# singleboard.net
KiCad netlist of a schematic drawn in EAGLE
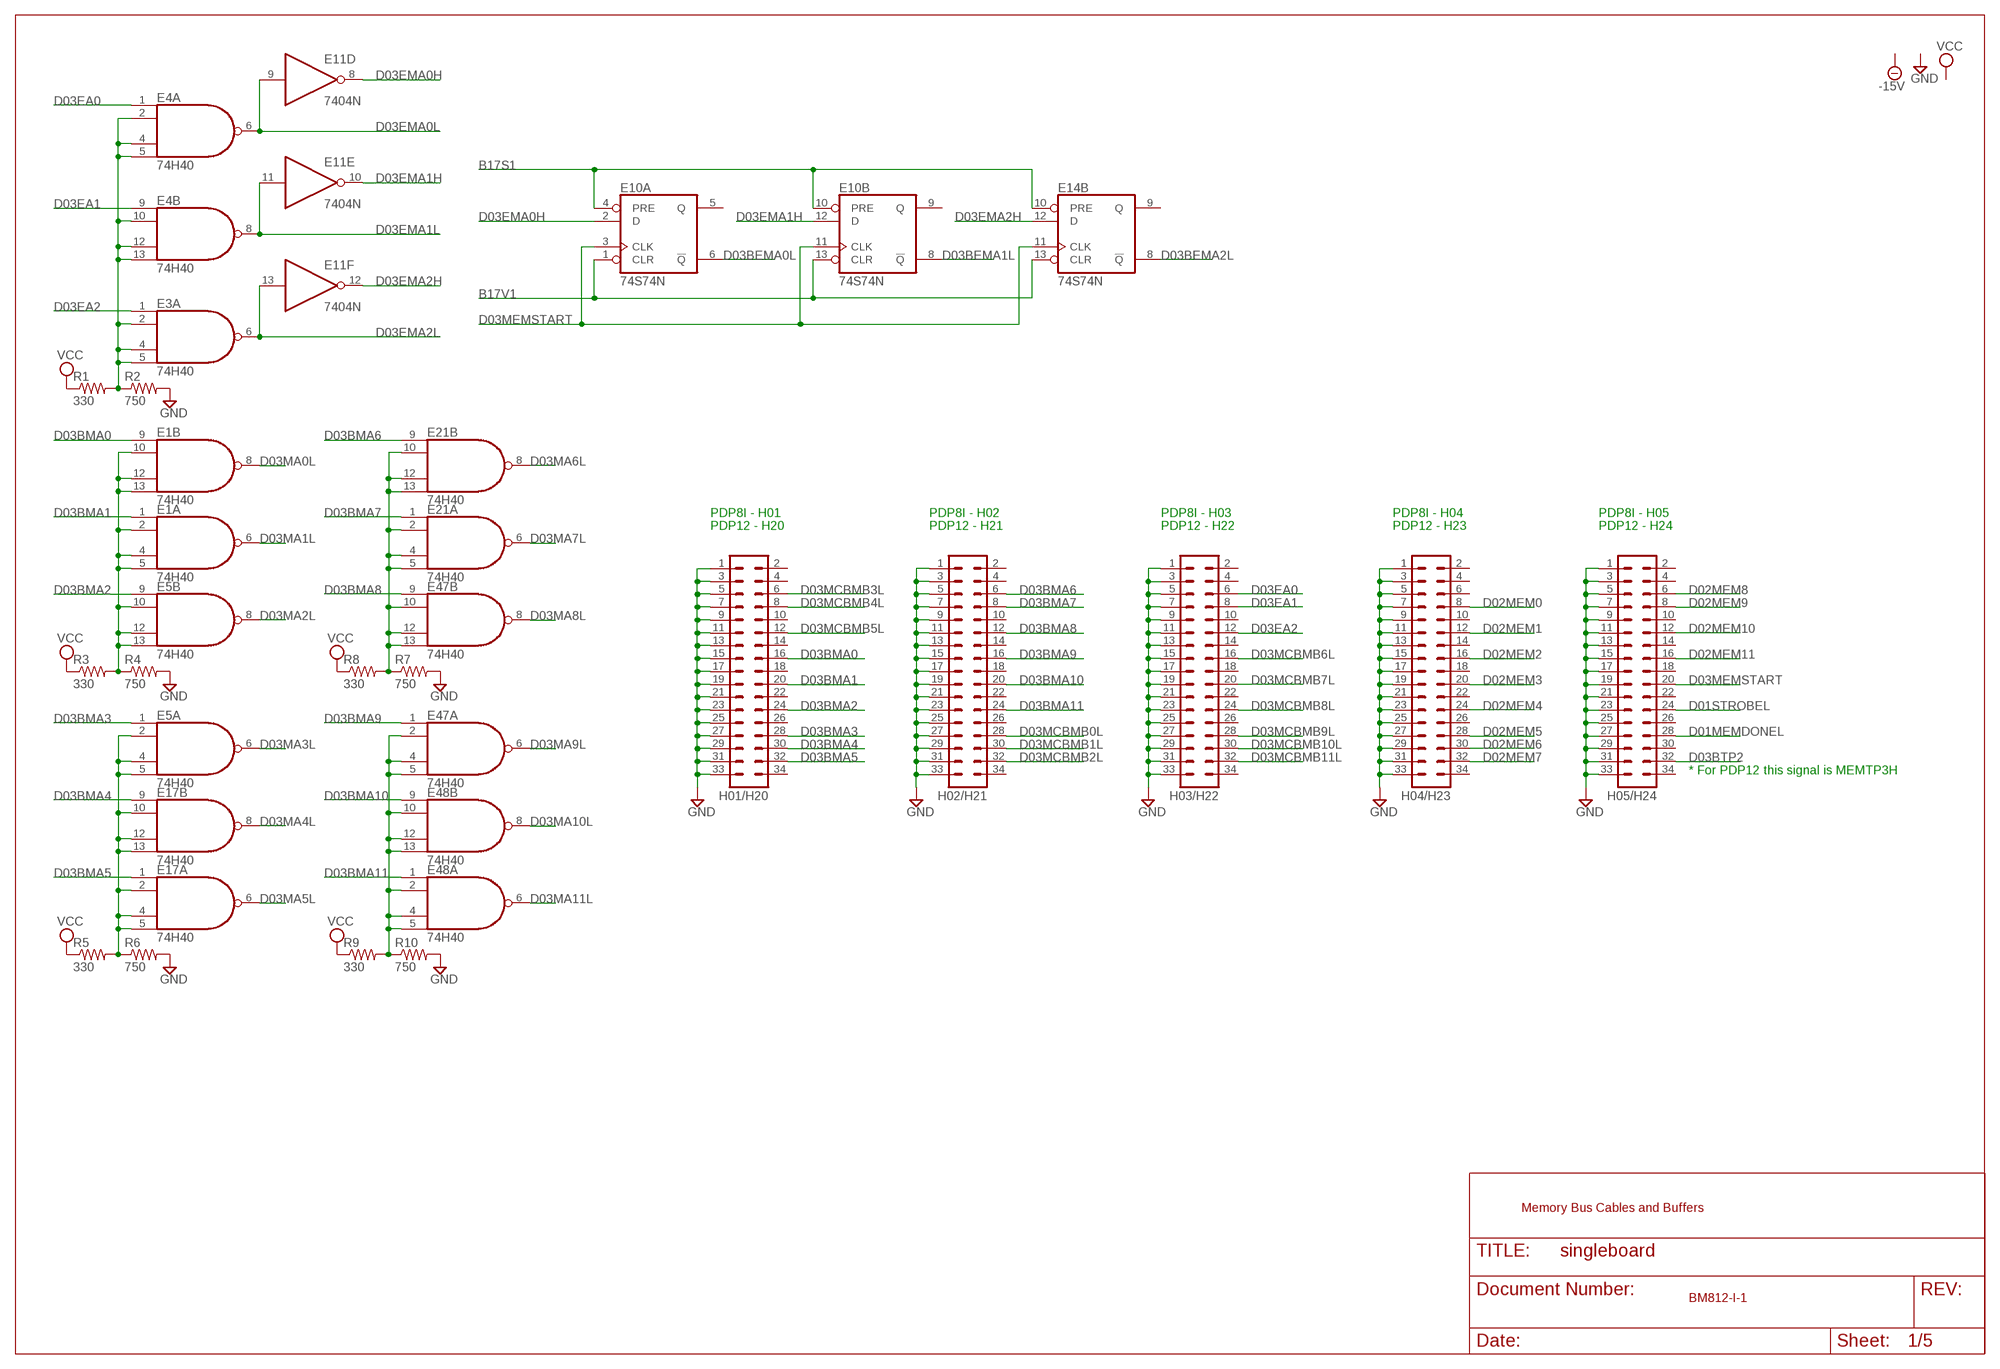
[diagram p0: schematic, sheet 1]
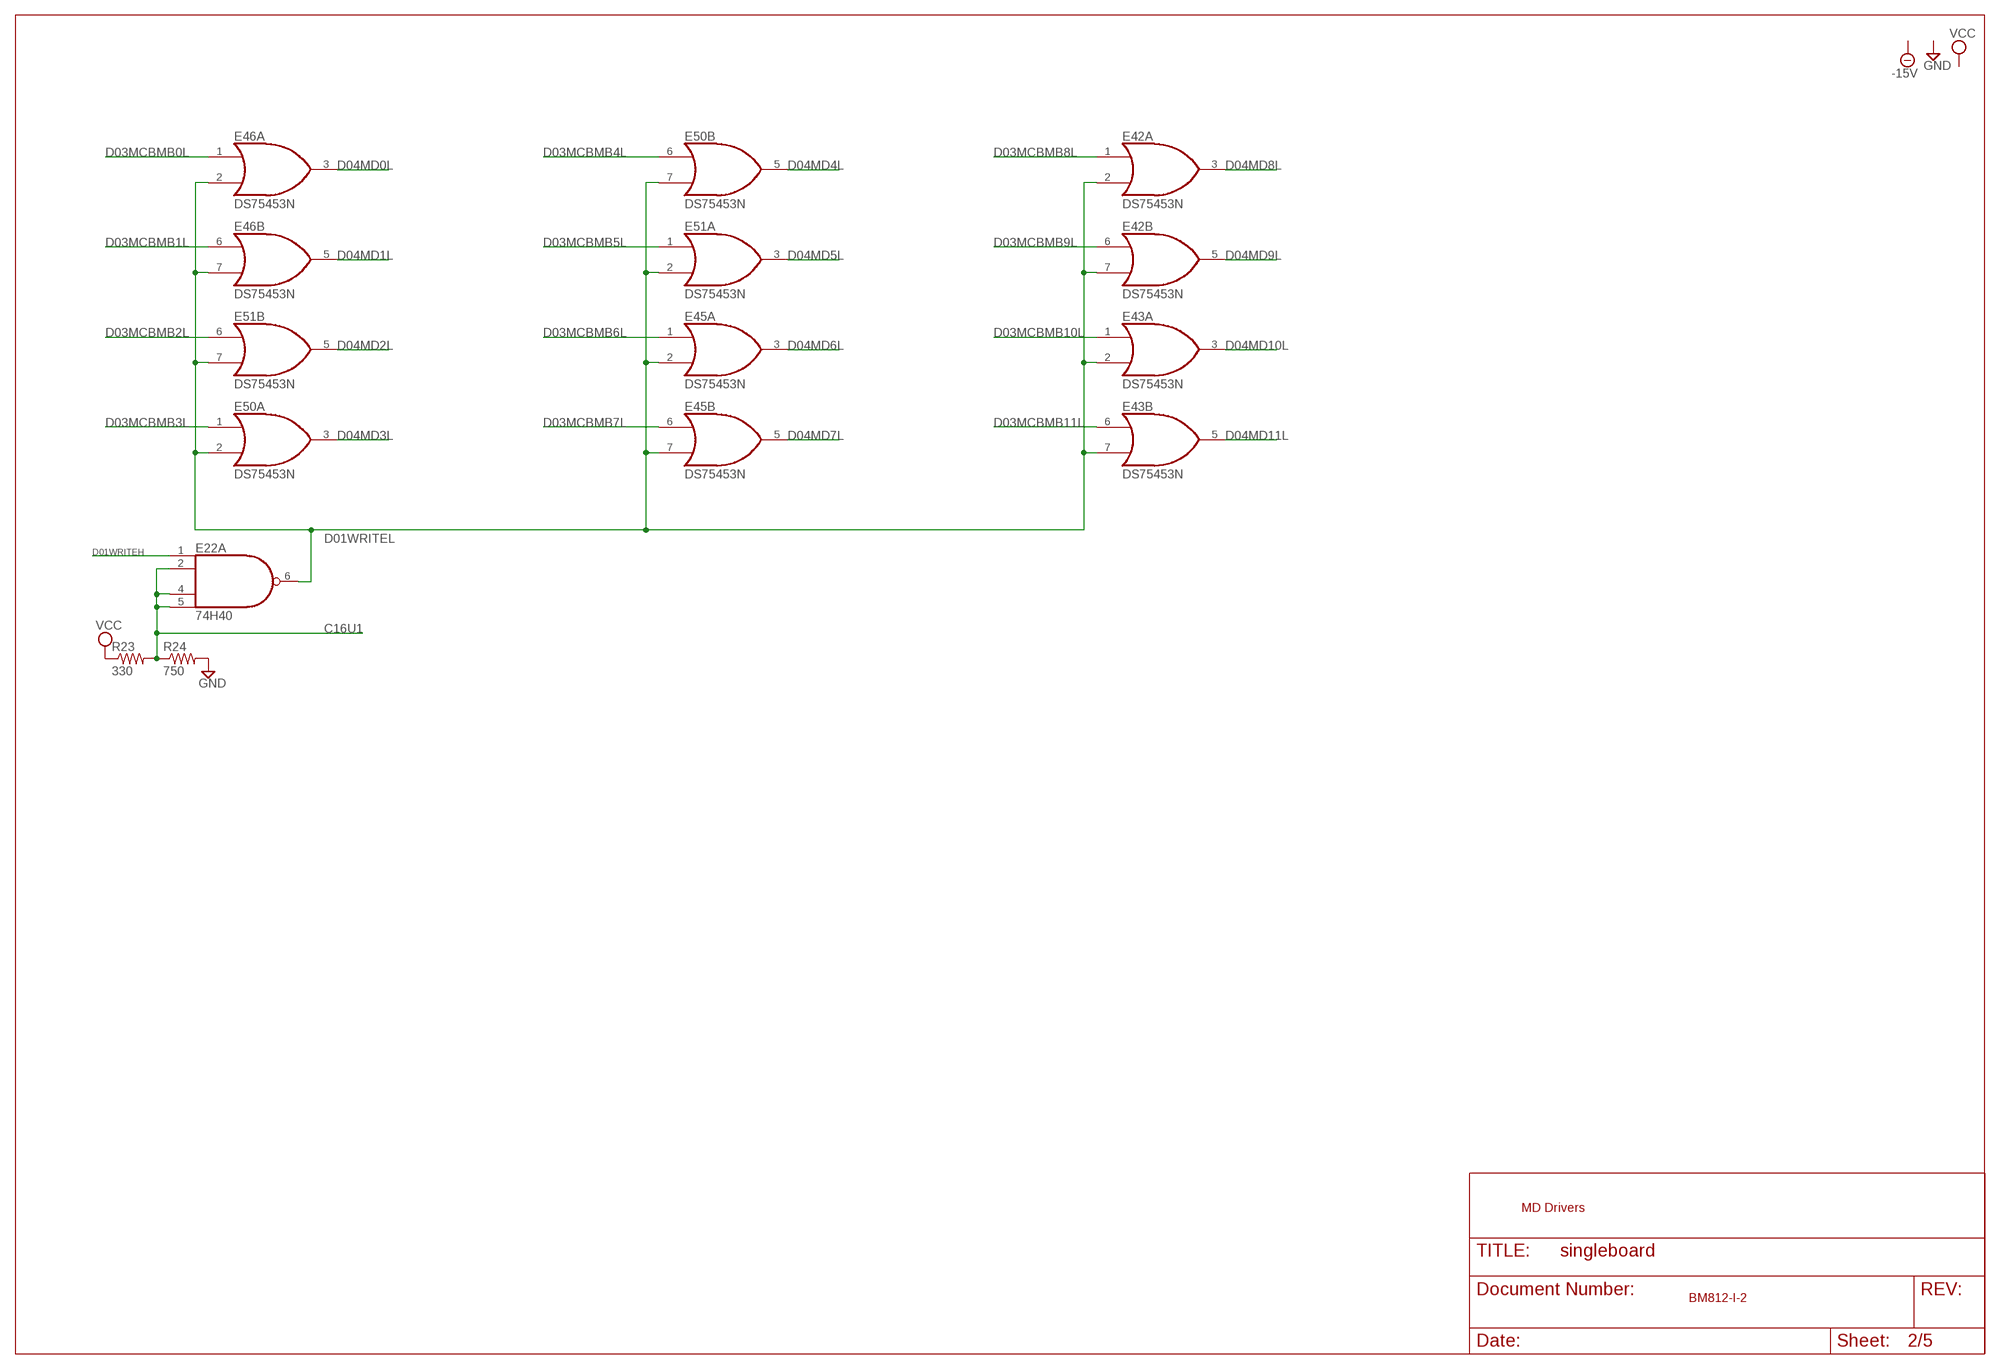
[diagram p1: schematic, sheet 2]
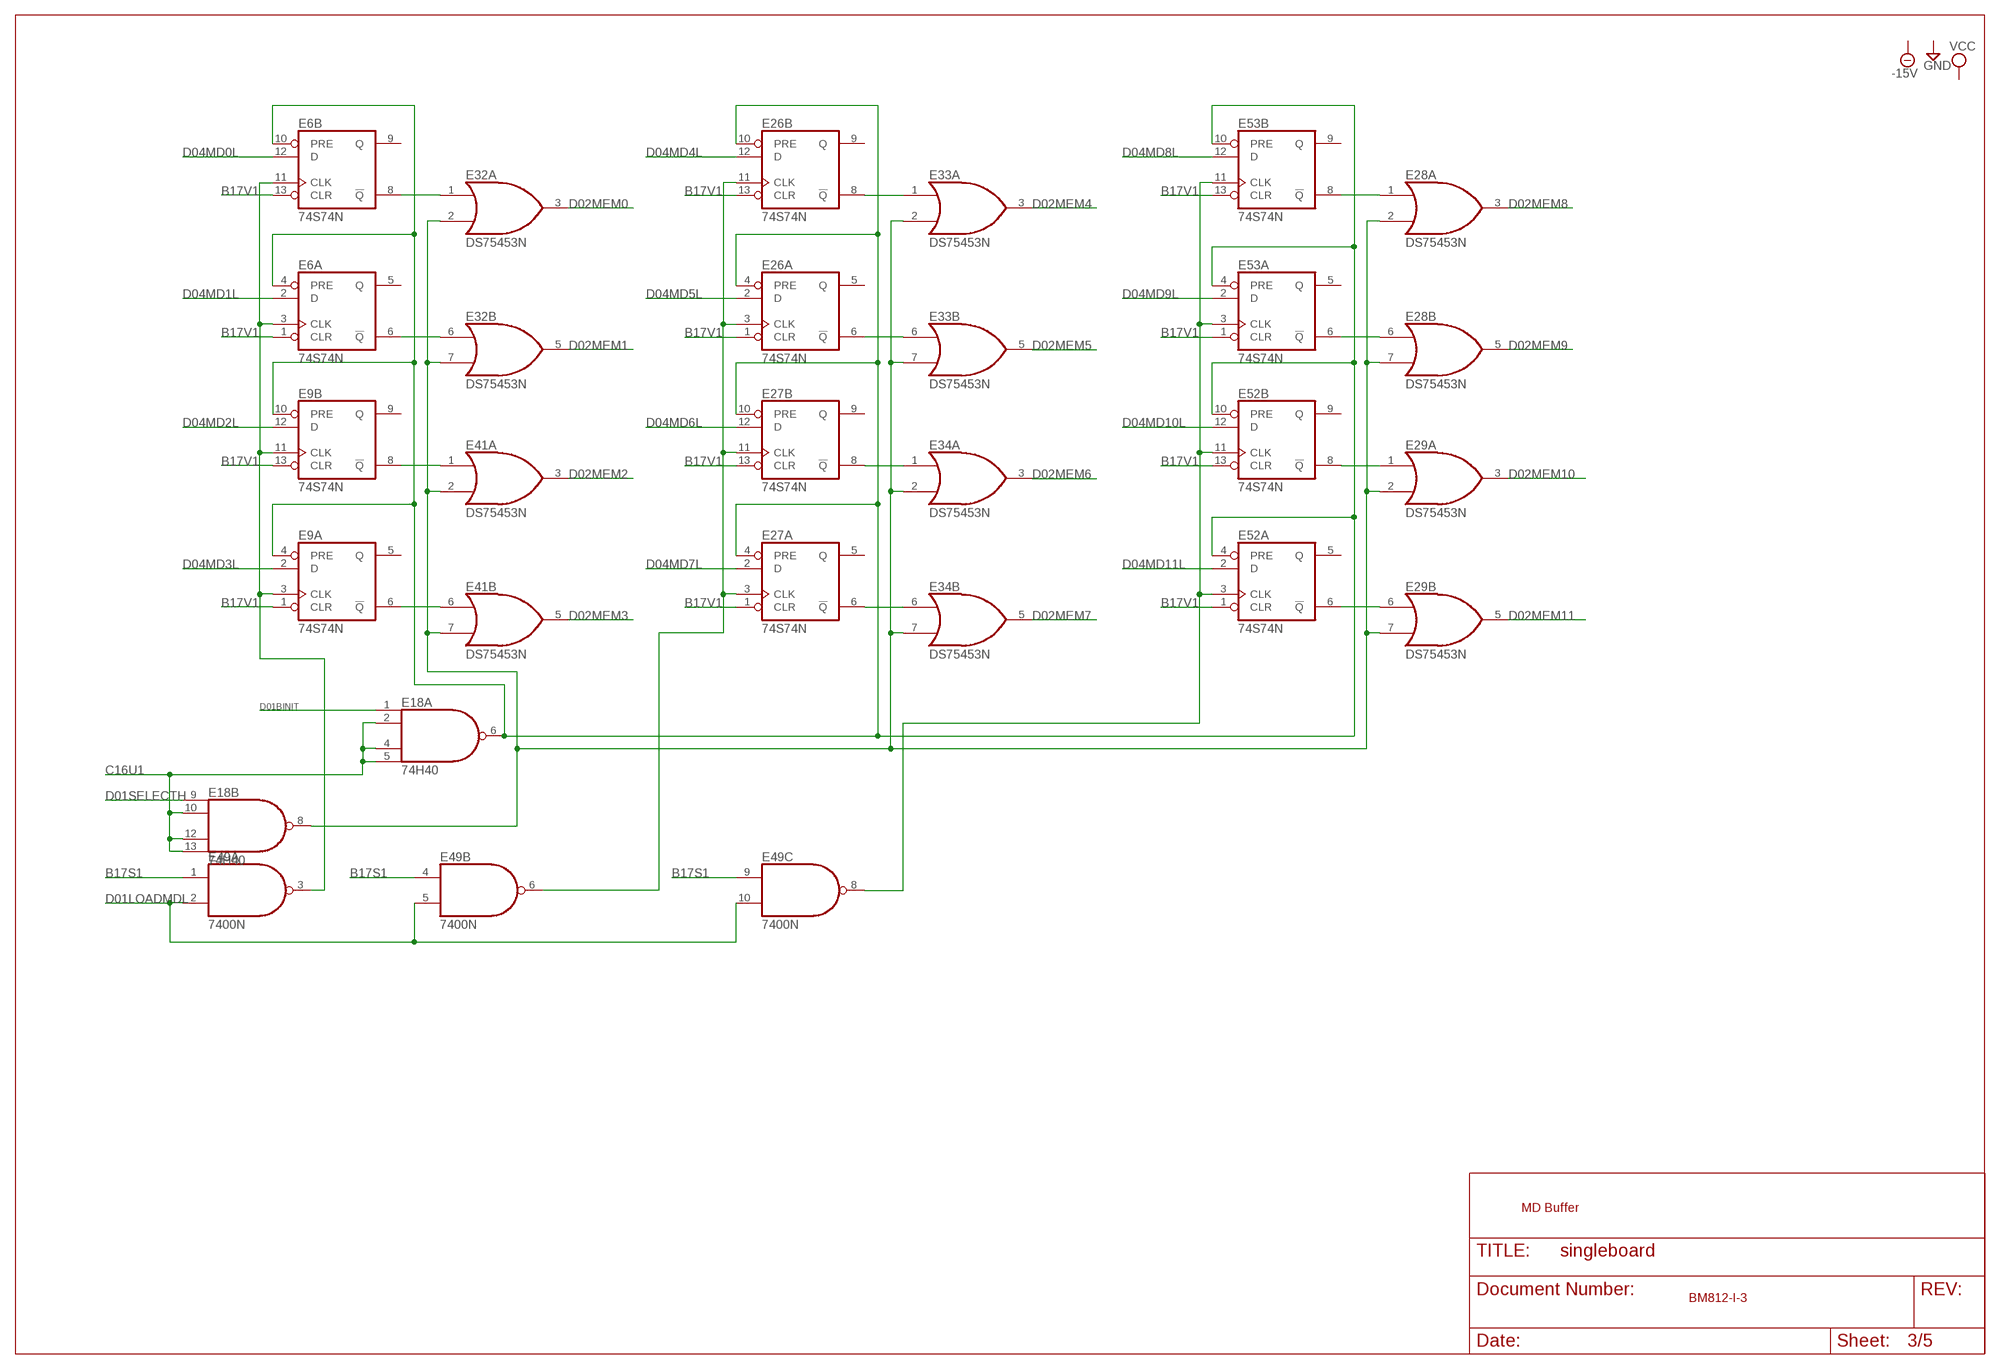
[diagram p2: schematic, sheet 3]
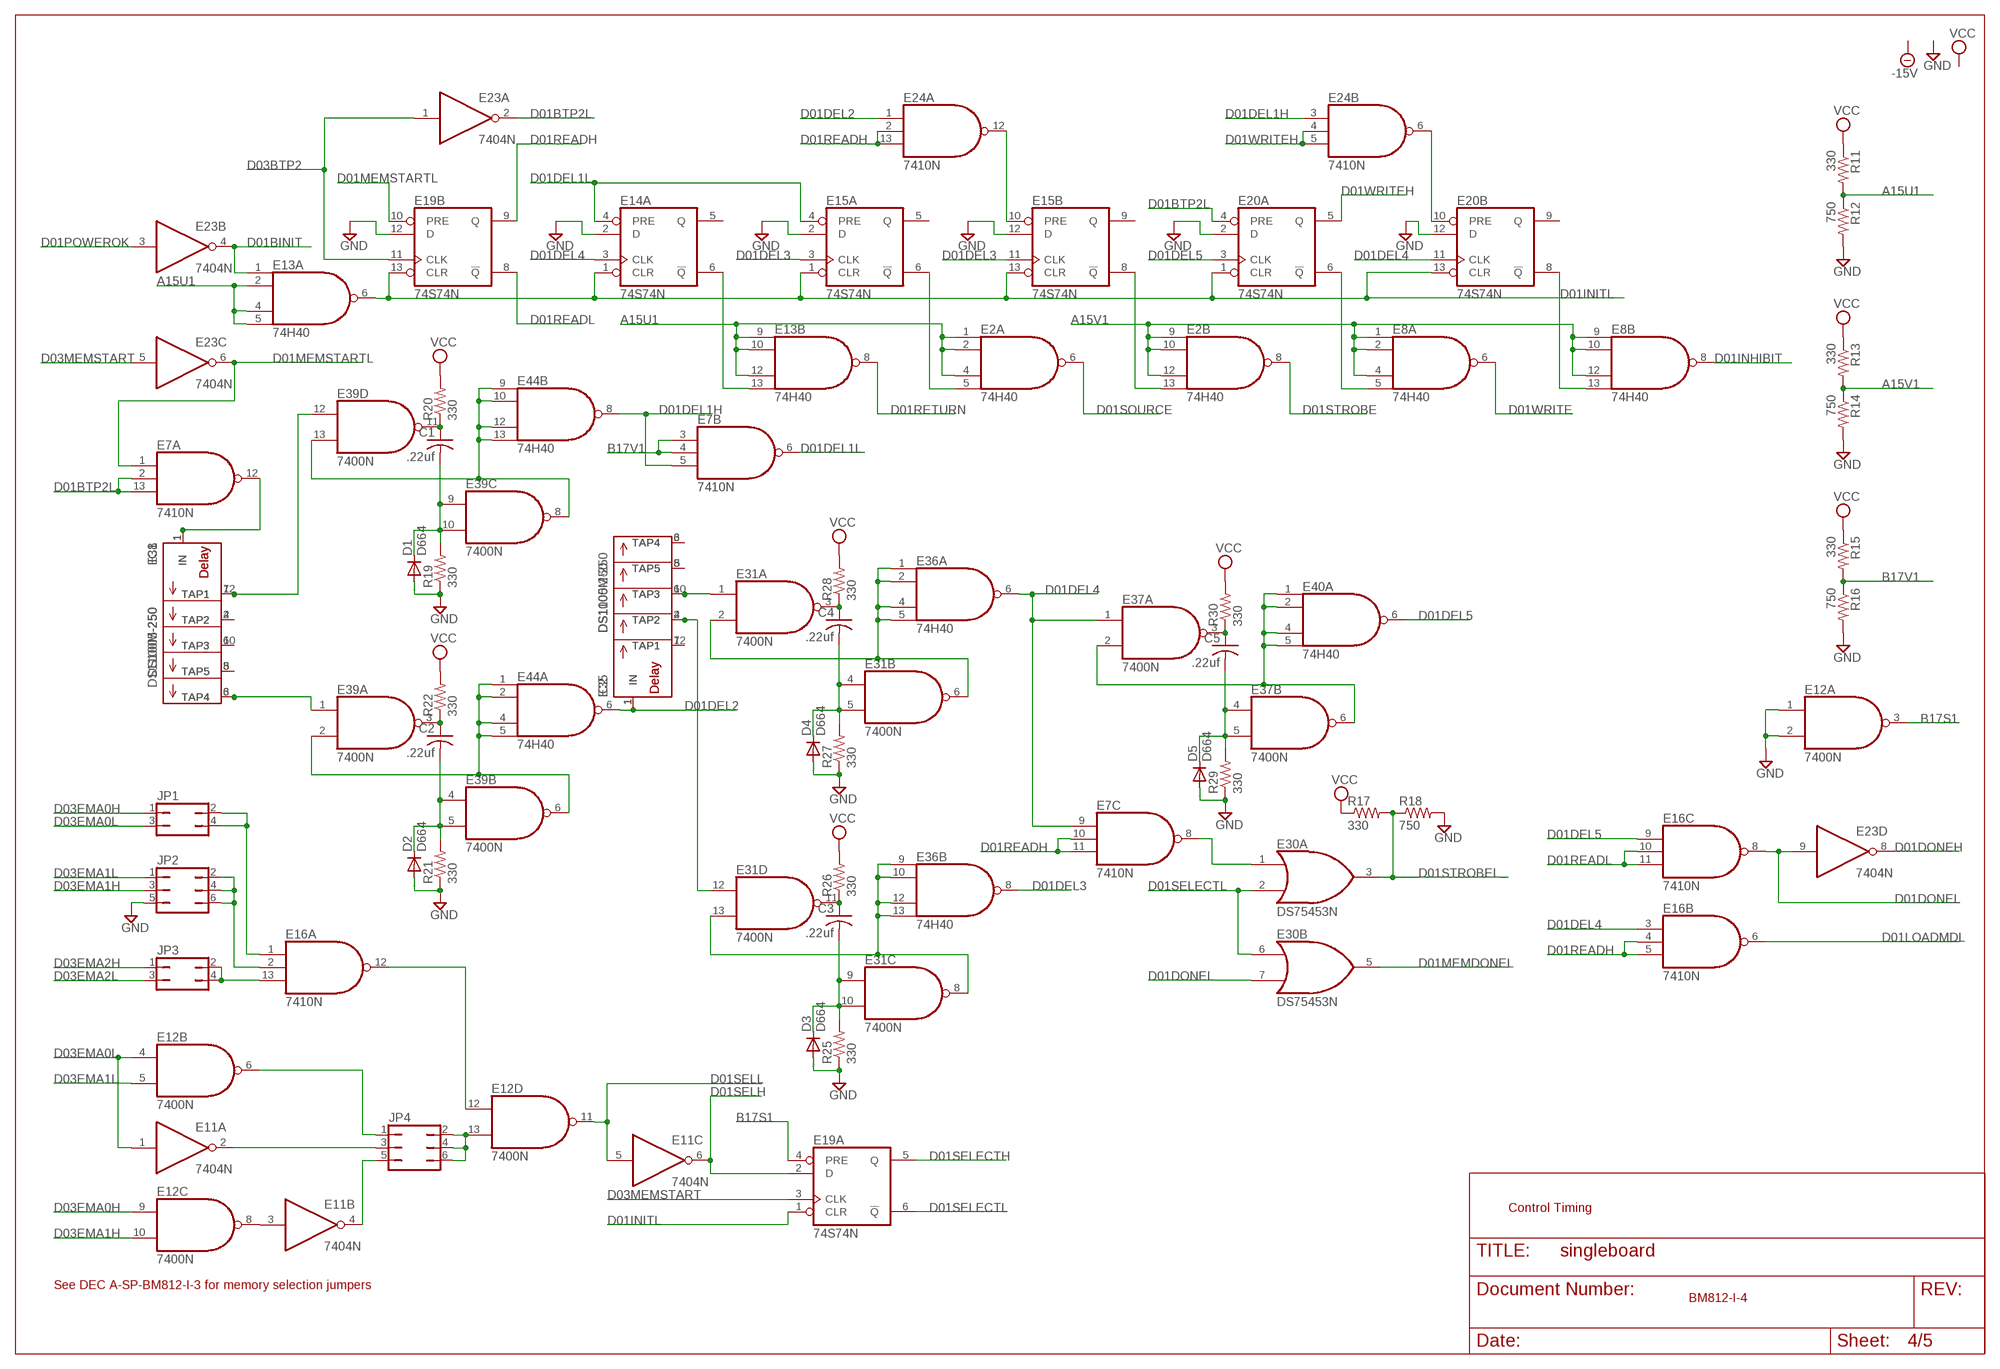
[diagram p3: schematic, sheet 4]
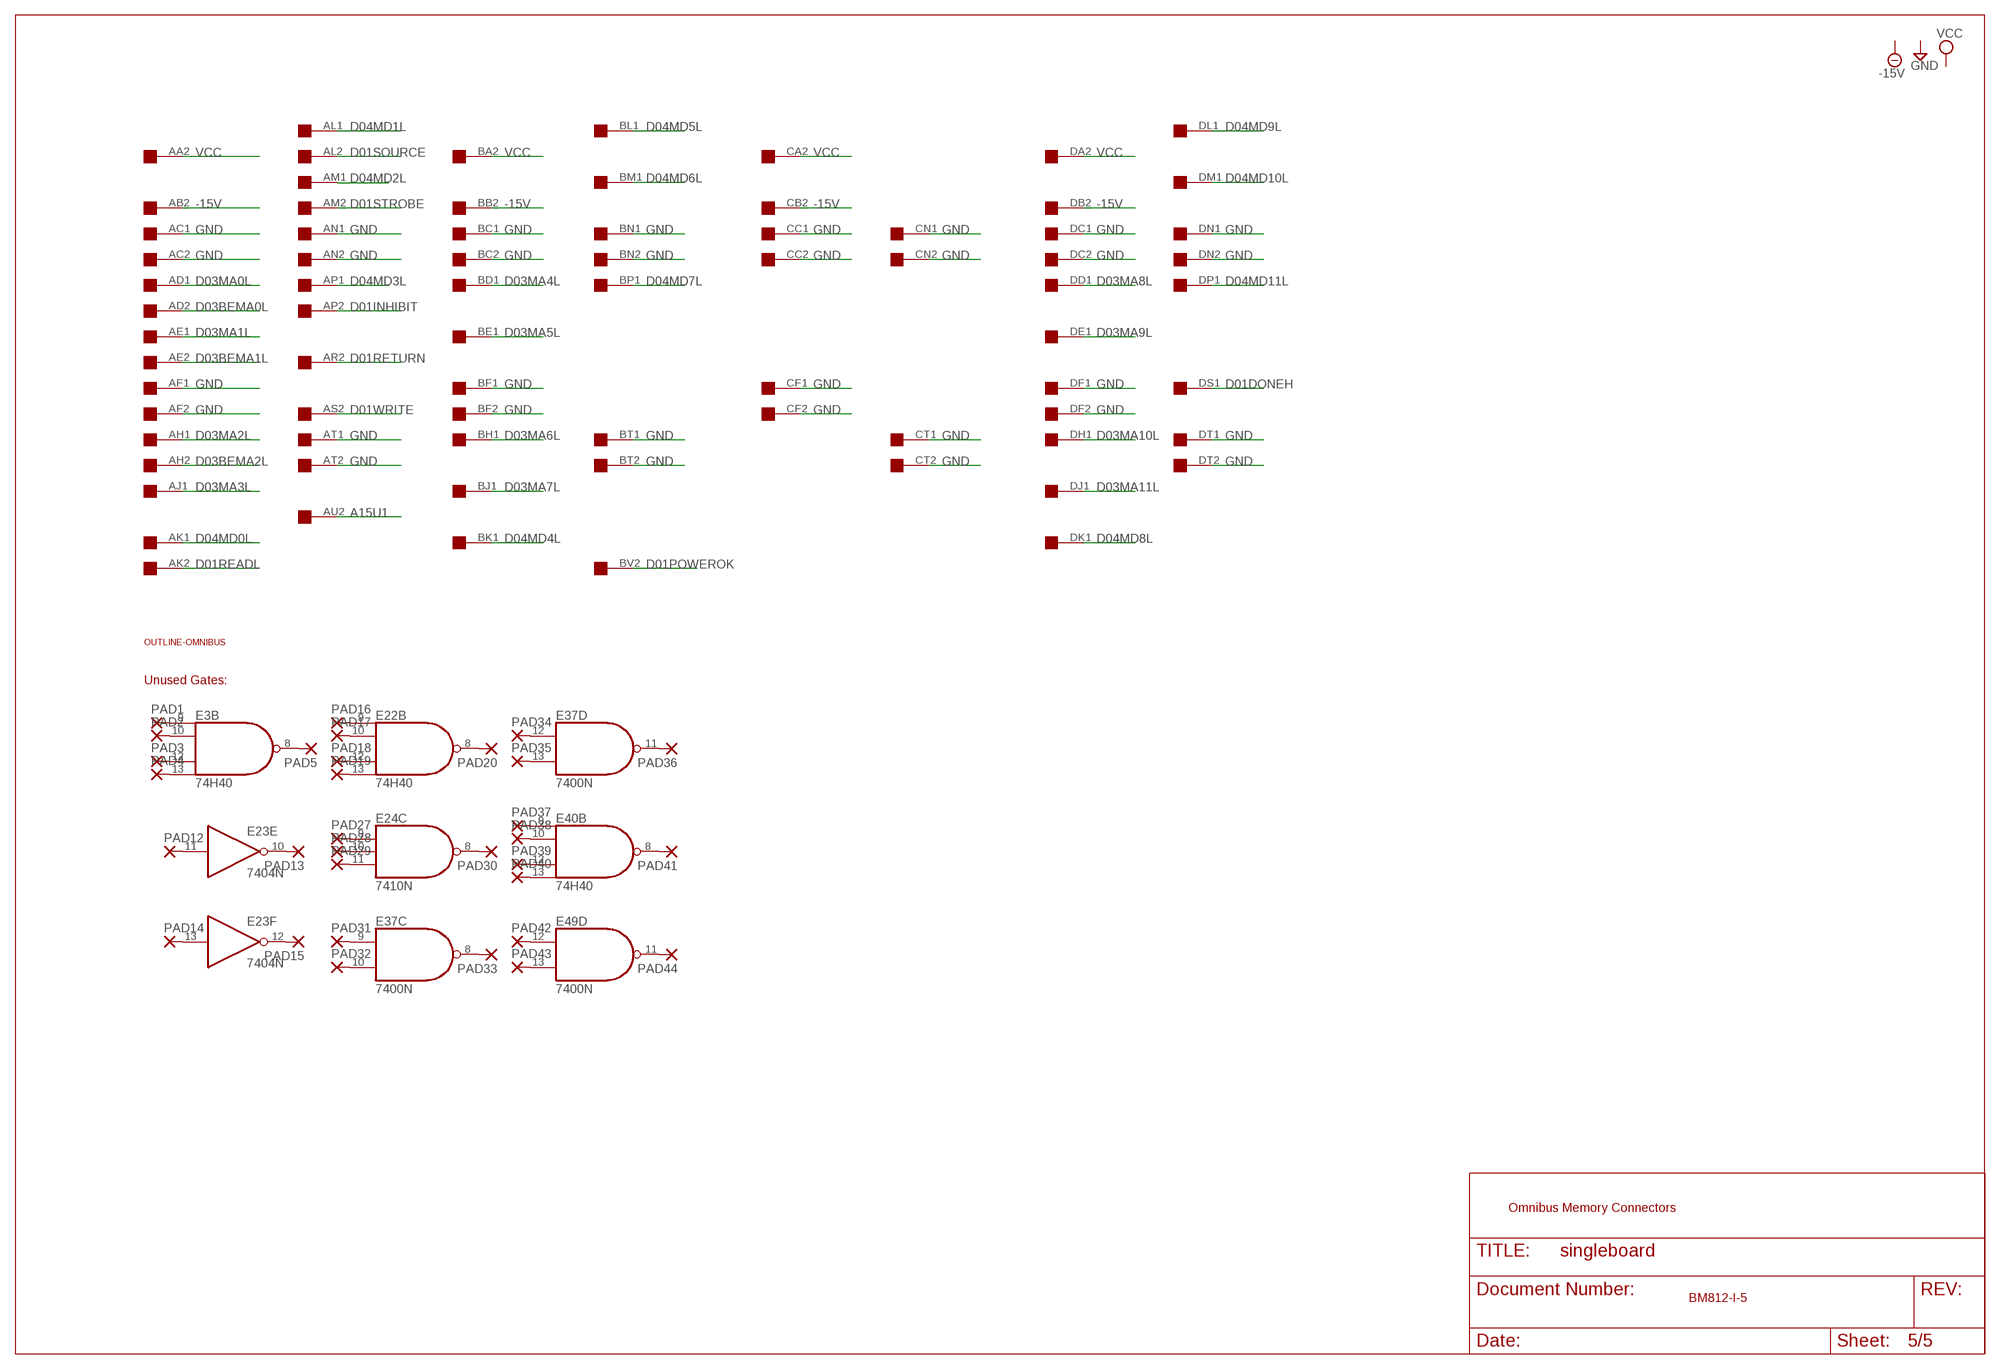
[diagram p4: schematic, sheet 5]

(export (version "E")
  (design (tool "Eeschema 10.0.6"))
  (components
    (comp (ref "E6")
      (value "74S74N")
      (footprint "eagle-import:DIL14")
      (libsource (lib "eagle-import") (part "7474NS"))
    )
    (comp (ref "E9")
      (value "74S74N")
      (footprint "eagle-import:DIL14")
      (libsource (lib "eagle-import") (part "7474NS"))
    )
    (comp (ref "E18")
      (value "74H40")
      (footprint "eagle-import:DIL14")
      (libsource (lib "eagle-import") (part "7420NS"))
    )
    (comp (ref "E26")
      (value "74S74N")
      (footprint "eagle-import:DIL14")
      (libsource (lib "eagle-import") (part "7474NS"))
    )
    (comp (ref "E27")
      (value "74S74N")
      (footprint "eagle-import:DIL14")
      (libsource (lib "eagle-import") (part "7474NS"))
    )
    (comp (ref "E28")
      (value "DS75453N")
      (footprint "eagle-import:DIL08")
      (libsource (lib "eagle-import") (part "DS75453N"))
    )
    (comp (ref "E29")
      (value "DS75453N")
      (footprint "eagle-import:DIL08")
      (libsource (lib "eagle-import") (part "DS75453N"))
    )
    (comp (ref "E32")
      (value "DS75453N")
      (footprint "eagle-import:DIL08")
      (libsource (lib "eagle-import") (part "DS75453N"))
    )
    (comp (ref "E33")
      (value "DS75453N")
      (footprint "eagle-import:DIL08")
      (libsource (lib "eagle-import") (part "DS75453N"))
    )
    (comp (ref "E34")
      (value "DS75453N")
      (footprint "eagle-import:DIL08")
      (libsource (lib "eagle-import") (part "DS75453N"))
    )
    (comp (ref "E41")
      (value "DS75453N")
      (footprint "eagle-import:DIL08")
      (libsource (lib "eagle-import") (part "DS75453N"))
    )
    (comp (ref "E49")
      (value "7400N")
      (footprint "eagle-import:DIL14")
      (libsource (lib "eagle-import") (part "7400N"))
    )
    (comp (ref "E52")
      (value "74S74N")
      (footprint "eagle-import:DIL14")
      (libsource (lib "eagle-import") (part "7474NS"))
    )
    (comp (ref "E53")
      (value "74S74N")
      (footprint "eagle-import:DIL14")
      (libsource (lib "eagle-import") (part "7474NS"))
    )
    (comp (ref "E22")
      (value "74H40")
      (footprint "eagle-import:DIL14")
      (libsource (lib "eagle-import") (part "7420NS"))
    )
    (comp (ref "E42")
      (value "DS75453N")
      (footprint "eagle-import:DIL08")
      (libsource (lib "eagle-import") (part "DS75453N"))
    )
    (comp (ref "E43")
      (value "DS75453N")
      (footprint "eagle-import:DIL08")
      (libsource (lib "eagle-import") (part "DS75453N"))
    )
    (comp (ref "E45")
      (value "DS75453N")
      (footprint "eagle-import:DIL08")
      (libsource (lib "eagle-import") (part "DS75453N"))
    )
    (comp (ref "E46")
      (value "DS75453N")
      (footprint "eagle-import:DIL08")
      (libsource (lib "eagle-import") (part "DS75453N"))
    )
    (comp (ref "E50")
      (value "DS75453N")
      (footprint "eagle-import:DIL08")
      (libsource (lib "eagle-import") (part "DS75453N"))
    )
    (comp (ref "E51")
      (value "DS75453N")
      (footprint "eagle-import:DIL08")
      (libsource (lib "eagle-import") (part "DS75453N"))
    )
    (comp (ref "R23")
      (value "330")
      (footprint "eagle-import:0207_10")
      (libsource (lib "eagle-import") (part "R-US_0207/10"))
    )
    (comp (ref "R24")
      (value "750")
      (footprint "eagle-import:0207_10")
      (libsource (lib "eagle-import") (part "R-US_0207/10"))
    )
    (comp (ref "E3")
      (value "74H40")
      (footprint "eagle-import:DIL14")
      (libsource (lib "eagle-import") (part "7420NS"))
    )
    (comp (ref "E23")
      (value "7404N")
      (footprint "eagle-import:DIL14")
      (libsource (lib "eagle-import") (part "7404N"))
    )
    (comp (ref "E24")
      (value "7410N")
      (footprint "eagle-import:DIL14")
      (libsource (lib "eagle-import") (part "7410N"))
    )
    (comp (ref "E37")
      (value "7400N")
      (footprint "eagle-import:DIL14")
      (libsource (lib "eagle-import") (part "7400N"))
    )
    (comp (ref "E40")
      (value "74H40")
      (footprint "eagle-import:DIL14")
      (libsource (lib "eagle-import") (part "7420NS"))
    )
    (comp (ref "PAD1")
      (value "1,6/0,8")
      (footprint "eagle-import:1,6_0,8")
      (libsource (lib "eagle-import") (part "1,6/0,8"))
    )
    (comp (ref "PAD2")
      (value "1,6/0,8")
      (footprint "eagle-import:1,6_0,8")
      (libsource (lib "eagle-import") (part "1,6/0,8"))
    )
    (comp (ref "PAD3")
      (value "1,6/0,8")
      (footprint "eagle-import:1,6_0,8")
      (libsource (lib "eagle-import") (part "1,6/0,8"))
    )
    (comp (ref "PAD4")
      (value "1,6/0,8")
      (footprint "eagle-import:1,6_0,8")
      (libsource (lib "eagle-import") (part "1,6/0,8"))
    )
    (comp (ref "PAD5")
      (value "1,6/0,8")
      (footprint "eagle-import:1,6_0,8")
      (libsource (lib "eagle-import") (part "1,6/0,8"))
    )
    (comp (ref "PAD12")
      (value "1,6/0,8")
      (footprint "eagle-import:1,6_0,8")
      (libsource (lib "eagle-import") (part "1,6/0,8"))
    )
    (comp (ref "PAD13")
      (value "1,6/0,8")
      (footprint "eagle-import:1,6_0,8")
      (libsource (lib "eagle-import") (part "1,6/0,8"))
    )
    (comp (ref "PAD14")
      (value "1,6/0,8")
      (footprint "eagle-import:1,6_0,8")
      (libsource (lib "eagle-import") (part "1,6/0,8"))
    )
    (comp (ref "PAD15")
      (value "1,6/0,8")
      (footprint "eagle-import:1,6_0,8")
      (libsource (lib "eagle-import") (part "1,6/0,8"))
    )
    (comp (ref "PAD16")
      (value "1,6/0,8")
      (footprint "eagle-import:1,6_0,8")
      (libsource (lib "eagle-import") (part "1,6/0,8"))
    )
    (comp (ref "PAD17")
      (value "1,6/0,8")
      (footprint "eagle-import:1,6_0,8")
      (libsource (lib "eagle-import") (part "1,6/0,8"))
    )
    (comp (ref "PAD18")
      (value "1,6/0,8")
      (footprint "eagle-import:1,6_0,8")
      (libsource (lib "eagle-import") (part "1,6/0,8"))
    )
    (comp (ref "PAD19")
      (value "1,6/0,8")
      (footprint "eagle-import:1,6_0,8")
      (libsource (lib "eagle-import") (part "1,6/0,8"))
    )
    (comp (ref "PAD20")
      (value "1,6/0,8")
      (footprint "eagle-import:1,6_0,8")
      (libsource (lib "eagle-import") (part "1,6/0,8"))
    )
    (comp (ref "PAD27")
      (value "1,6/0,8")
      (footprint "eagle-import:1,6_0,8")
      (libsource (lib "eagle-import") (part "1,6/0,8"))
    )
    (comp (ref "PAD28")
      (value "1,6/0,8")
      (footprint "eagle-import:1,6_0,8")
      (libsource (lib "eagle-import") (part "1,6/0,8"))
    )
    (comp (ref "PAD29")
      (value "1,6/0,8")
      (footprint "eagle-import:1,6_0,8")
      (libsource (lib "eagle-import") (part "1,6/0,8"))
    )
    (comp (ref "PAD30")
      (value "1,6/0,8")
      (footprint "eagle-import:1,6_0,8")
      (libsource (lib "eagle-import") (part "1,6/0,8"))
    )
    (comp (ref "PAD31")
      (value "1,6/0,8")
      (footprint "eagle-import:1,6_0,8")
      (libsource (lib "eagle-import") (part "1,6/0,8"))
    )
    (comp (ref "PAD32")
      (value "1,6/0,8")
      (footprint "eagle-import:1,6_0,8")
      (libsource (lib "eagle-import") (part "1,6/0,8"))
    )
    (comp (ref "PAD33")
      (value "1,6/0,8")
      (footprint "eagle-import:1,6_0,8")
      (libsource (lib "eagle-import") (part "1,6/0,8"))
    )
    (comp (ref "PAD34")
      (value "1,6/0,8")
      (footprint "eagle-import:1,6_0,8")
      (libsource (lib "eagle-import") (part "1,6/0,8"))
    )
    (comp (ref "PAD35")
      (value "1,6/0,8")
      (footprint "eagle-import:1,6_0,8")
      (libsource (lib "eagle-import") (part "1,6/0,8"))
    )
    (comp (ref "PAD36")
      (value "1,6/0,8")
      (footprint "eagle-import:1,6_0,8")
      (libsource (lib "eagle-import") (part "1,6/0,8"))
    )
    (comp (ref "PAD37")
      (value "1,6/0,8")
      (footprint "eagle-import:1,6_0,8")
      (libsource (lib "eagle-import") (part "1,6/0,8"))
    )
    (comp (ref "PAD38")
      (value "1,6/0,8")
      (footprint "eagle-import:1,6_0,8")
      (libsource (lib "eagle-import") (part "1,6/0,8"))
    )
    (comp (ref "PAD39")
      (value "1,6/0,8")
      (footprint "eagle-import:1,6_0,8")
      (libsource (lib "eagle-import") (part "1,6/0,8"))
    )
    (comp (ref "PAD40")
      (value "1,6/0,8")
      (footprint "eagle-import:1,6_0,8")
      (libsource (lib "eagle-import") (part "1,6/0,8"))
    )
    (comp (ref "PAD41")
      (value "1,6/0,8")
      (footprint "eagle-import:1,6_0,8")
      (libsource (lib "eagle-import") (part "1,6/0,8"))
    )
    (comp (ref "PAD42")
      (value "1,6/0,8")
      (footprint "eagle-import:1,6_0,8")
      (libsource (lib "eagle-import") (part "1,6/0,8"))
    )
    (comp (ref "PAD43")
      (value "1,6/0,8")
      (footprint "eagle-import:1,6_0,8")
      (libsource (lib "eagle-import") (part "1,6/0,8"))
    )
    (comp (ref "PAD44")
      (value "1,6/0,8")
      (footprint "eagle-import:1,6_0,8")
      (libsource (lib "eagle-import") (part "1,6/0,8"))
    )
    (comp (ref "U$1")
      (value "QUAD")
      (footprint "eagle-import:EDGE-CON8")
      (libsource (lib "eagle-import") (part "QUAD"))
    )
    (comp (ref "U$2")
      (value "OUTLINE-OMNIBUS")
      (footprint "eagle-import:OMNIBUS")
      (libsource (lib "eagle-import") (part "OUTLINE-OMNIBUS"))
    )
    (comp (ref "C1")
      (value ".22uf")
      (footprint "eagle-import:C050-025X075")
      (libsource (lib "eagle-import") (part "C-US050-025X075"))
    )
    (comp (ref "C2")
      (value ".22uf")
      (footprint "eagle-import:C050-025X075")
      (libsource (lib "eagle-import") (part "C-US050-025X075"))
    )
    (comp (ref "C3")
      (value ".22uf")
      (footprint "eagle-import:C050-025X075")
      (libsource (lib "eagle-import") (part "C-US050-025X075"))
    )
    (comp (ref "C4")
      (value ".22uf")
      (footprint "eagle-import:C050-025X075")
      (libsource (lib "eagle-import") (part "C-US050-025X075"))
    )
    (comp (ref "C5")
      (value ".22uf")
      (footprint "eagle-import:C050-025X075")
      (libsource (lib "eagle-import") (part "C-US050-025X075"))
    )
    (comp (ref "D1")
      (value "D664")
      (footprint "eagle-import:DO35-10")
      (libsource (lib "eagle-import") (part "1N4148DO35-10"))
    )
    (comp (ref "D2")
      (value "D664")
      (footprint "eagle-import:DO35-10")
      (libsource (lib "eagle-import") (part "1N4148DO35-10"))
    )
    (comp (ref "D3")
      (value "D664")
      (footprint "eagle-import:DO35-10")
      (libsource (lib "eagle-import") (part "1N4148DO35-10"))
    )
    (comp (ref "D4")
      (value "D664")
      (footprint "eagle-import:DO35-10")
      (libsource (lib "eagle-import") (part "1N4148DO35-10"))
    )
    (comp (ref "D5")
      (value "D664")
      (footprint "eagle-import:DO35-10")
      (libsource (lib "eagle-import") (part "1N4148DO35-10"))
    )
    (comp (ref "E2")
      (value "74H40")
      (footprint "eagle-import:DIL14")
      (libsource (lib "eagle-import") (part "7420NS"))
    )
    (comp (ref "E7")
      (value "7410N")
      (footprint "eagle-import:DIL14")
      (libsource (lib "eagle-import") (part "7410N"))
    )
    (comp (ref "E8")
      (value "74H40")
      (footprint "eagle-import:DIL14")
      (libsource (lib "eagle-import") (part "7420NS"))
    )
    (comp (ref "E11")
      (value "7404N")
      (footprint "eagle-import:DIL14")
      (libsource (lib "eagle-import") (part "7404N"))
    )
    (comp (ref "E12")
      (value "7400N")
      (footprint "eagle-import:DIL14")
      (libsource (lib "eagle-import") (part "7400N"))
    )
    (comp (ref "E13")
      (value "74H40")
      (footprint "eagle-import:DIL14")
      (libsource (lib "eagle-import") (part "7420NS"))
    )
    (comp (ref "E14")
      (value "74S74N")
      (footprint "eagle-import:DIL14")
      (libsource (lib "eagle-import") (part "7474NS"))
    )
    (comp (ref "E15")
      (value "74S74N")
      (footprint "eagle-import:DIL14")
      (libsource (lib "eagle-import") (part "7474NS"))
    )
    (comp (ref "E16")
      (value "7410N")
      (footprint "eagle-import:DIL14")
      (libsource (lib "eagle-import") (part "7410N"))
    )
    (comp (ref "E19")
      (value "74S74N")
      (footprint "eagle-import:DIL14")
      (libsource (lib "eagle-import") (part "7474NS"))
    )
    (comp (ref "E20")
      (value "74S74N")
      (footprint "eagle-import:DIL14")
      (libsource (lib "eagle-import") (part "7474NS"))
    )
    (comp (ref "E30")
      (value "DS75453N")
      (footprint "eagle-import:DIL08")
      (libsource (lib "eagle-import") (part "DS75453N"))
    )
    (comp (ref "E31")
      (value "7400N")
      (footprint "eagle-import:DIL14")
      (libsource (lib "eagle-import") (part "7400N"))
    )
    (comp (ref "E35")
      (value "DS1005-250")
      (footprint "eagle-import:DIL14")
      (libsource (lib "eagle-import") (part "MXD1000P"))
    )
    (comp (ref "E36")
      (value "74H40")
      (footprint "eagle-import:DIL14")
      (libsource (lib "eagle-import") (part "7420NS"))
    )
    (comp (ref "E38")
      (value "DS1005-250")
      (footprint "eagle-import:DIL14")
      (libsource (lib "eagle-import") (part "MXD1000P"))
    )
    (comp (ref "E39")
      (value "7400N")
      (footprint "eagle-import:DIL14")
      (libsource (lib "eagle-import") (part "7400N"))
    )
    (comp (ref "E44")
      (value "74H40")
      (footprint "eagle-import:DIL14")
      (libsource (lib "eagle-import") (part "7420NS"))
    )
    (comp (ref "IC1")
      (value "DS1100M-250")
      (footprint "eagle-import:DIL08")
      (libsource (lib "eagle-import") (part "MXD1000"))
    )
    (comp (ref "IC2")
      (value "DS1100M-250")
      (footprint "eagle-import:DIL08")
      (libsource (lib "eagle-import") (part "MXD1000"))
    )
    (comp (ref "JP1")
      (value "JP2Q")
      (footprint "eagle-import:JP2Q")
      (libsource (lib "eagle-import") (part "JP2Q"))
    )
    (comp (ref "JP2")
      (value "JP3Q")
      (footprint "eagle-import:JP3Q")
      (libsource (lib "eagle-import") (part "JP3Q"))
    )
    (comp (ref "JP3")
      (value "JP2Q")
      (footprint "eagle-import:JP2Q")
      (libsource (lib "eagle-import") (part "JP2Q"))
    )
    (comp (ref "JP4")
      (value "JP3Q")
      (footprint "eagle-import:JP3Q")
      (libsource (lib "eagle-import") (part "JP3Q"))
    )
    (comp (ref "R11")
      (value "330")
      (footprint "eagle-import:0207_10")
      (libsource (lib "eagle-import") (part "R-US_0207/10"))
    )
    (comp (ref "R12")
      (value "750")
      (footprint "eagle-import:0207_10")
      (libsource (lib "eagle-import") (part "R-US_0207/10"))
    )
    (comp (ref "R13")
      (value "330")
      (footprint "eagle-import:0207_10")
      (libsource (lib "eagle-import") (part "R-US_0207/10"))
    )
    (comp (ref "R14")
      (value "750")
      (footprint "eagle-import:0207_10")
      (libsource (lib "eagle-import") (part "R-US_0207/10"))
    )
    (comp (ref "R15")
      (value "330")
      (footprint "eagle-import:0207_10")
      (libsource (lib "eagle-import") (part "R-US_0207/10"))
    )
    (comp (ref "R16")
      (value "750")
      (footprint "eagle-import:0207_10")
      (libsource (lib "eagle-import") (part "R-US_0207/10"))
    )
    (comp (ref "R17")
      (value "330")
      (footprint "eagle-import:0207_10")
      (libsource (lib "eagle-import") (part "R-US_0207/10"))
    )
    (comp (ref "R18")
      (value "750")
      (footprint "eagle-import:0207_10")
      (libsource (lib "eagle-import") (part "R-US_0207/10"))
    )
    (comp (ref "R19")
      (value "330")
      (footprint "eagle-import:0207_10")
      (libsource (lib "eagle-import") (part "R-US_0207/10"))
    )
    (comp (ref "R20")
      (value "330")
      (footprint "eagle-import:0207_10")
      (libsource (lib "eagle-import") (part "R-US_0207/10"))
    )
    (comp (ref "R21")
      (value "330")
      (footprint "eagle-import:0207_10")
      (libsource (lib "eagle-import") (part "R-US_0207/10"))
    )
    (comp (ref "R22")
      (value "330")
      (footprint "eagle-import:0207_10")
      (libsource (lib "eagle-import") (part "R-US_0207/10"))
    )
    (comp (ref "R25")
      (value "330")
      (footprint "eagle-import:0207_10")
      (libsource (lib "eagle-import") (part "R-US_0207/10"))
    )
    (comp (ref "R26")
      (value "330")
      (footprint "eagle-import:0207_10")
      (libsource (lib "eagle-import") (part "R-US_0207/10"))
    )
    (comp (ref "R27")
      (value "330")
      (footprint "eagle-import:0207_10")
      (libsource (lib "eagle-import") (part "R-US_0207/10"))
    )
    (comp (ref "R28")
      (value "330")
      (footprint "eagle-import:0207_10")
      (libsource (lib "eagle-import") (part "R-US_0207/10"))
    )
    (comp (ref "R29")
      (value "330")
      (footprint "eagle-import:0207_10")
      (libsource (lib "eagle-import") (part "R-US_0207/10"))
    )
    (comp (ref "R30")
      (value "330")
      (footprint "eagle-import:0207_10")
      (libsource (lib "eagle-import") (part "R-US_0207/10"))
    )
    (comp (ref "E1")
      (value "74H40")
      (footprint "eagle-import:DIL14")
      (libsource (lib "eagle-import") (part "7420NS"))
    )
    (comp (ref "E4")
      (value "74H40")
      (footprint "eagle-import:DIL14")
      (libsource (lib "eagle-import") (part "7420NS"))
    )
    (comp (ref "E5")
      (value "74H40")
      (footprint "eagle-import:DIL14")
      (libsource (lib "eagle-import") (part "7420NS"))
    )
    (comp (ref "E10")
      (value "74S74N")
      (footprint "eagle-import:DIL14")
      (libsource (lib "eagle-import") (part "7474NS"))
    )
    (comp (ref "E17")
      (value "74H40")
      (footprint "eagle-import:DIL14")
      (libsource (lib "eagle-import") (part "7420NS"))
    )
    (comp (ref "E21")
      (value "74H40")
      (footprint "eagle-import:DIL14")
      (libsource (lib "eagle-import") (part "7420NS"))
    )
    (comp (ref "E47")
      (value "74H40")
      (footprint "eagle-import:DIL14")
      (libsource (lib "eagle-import") (part "7420NS"))
    )
    (comp (ref "E48")
      (value "74H40")
      (footprint "eagle-import:DIL14")
      (libsource (lib "eagle-import") (part "7420NS"))
    )
    (comp (ref "H01/H20")
      (value "MA17-2")
      (footprint "eagle-import:MA17-2")
      (libsource (lib "eagle-import") (part "MA17-2"))
    )
    (comp (ref "H02/H21")
      (value "MA17-2")
      (footprint "eagle-import:MA17-2")
      (libsource (lib "eagle-import") (part "MA17-2"))
    )
    (comp (ref "H03/H22")
      (value "MA17-2")
      (footprint "eagle-import:MA17-2")
      (libsource (lib "eagle-import") (part "MA17-2"))
    )
    (comp (ref "H04/H23")
      (value "MA17-2")
      (footprint "eagle-import:MA17-2")
      (libsource (lib "eagle-import") (part "MA17-2"))
    )
    (comp (ref "H05/H24")
      (value "MA17-2")
      (footprint "eagle-import:MA17-2")
      (libsource (lib "eagle-import") (part "MA17-2"))
    )
    (comp (ref "R1")
      (value "330")
      (footprint "eagle-import:0207_10")
      (libsource (lib "eagle-import") (part "R-US_0207/10"))
    )
    (comp (ref "R2")
      (value "750")
      (footprint "eagle-import:0207_10")
      (libsource (lib "eagle-import") (part "R-US_0207/10"))
    )
    (comp (ref "R3")
      (value "330")
      (footprint "eagle-import:0207_10")
      (libsource (lib "eagle-import") (part "R-US_0207/10"))
    )
    (comp (ref "R4")
      (value "750")
      (footprint "eagle-import:0207_10")
      (libsource (lib "eagle-import") (part "R-US_0207/10"))
    )
    (comp (ref "R5")
      (value "330")
      (footprint "eagle-import:0207_10")
      (libsource (lib "eagle-import") (part "R-US_0207/10"))
    )
    (comp (ref "R6")
      (value "750")
      (footprint "eagle-import:0207_10")
      (libsource (lib "eagle-import") (part "R-US_0207/10"))
    )
    (comp (ref "R7")
      (value "750")
      (footprint "eagle-import:0207_10")
      (libsource (lib "eagle-import") (part "R-US_0207/10"))
    )
    (comp (ref "R8")
      (value "330")
      (footprint "eagle-import:0207_10")
      (libsource (lib "eagle-import") (part "R-US_0207/10"))
    )
    (comp (ref "R9")
      (value "330")
      (footprint "eagle-import:0207_10")
      (libsource (lib "eagle-import") (part "R-US_0207/10"))
    )
    (comp (ref "R10")
      (value "750")
      (footprint "eagle-import:0207_10")
      (libsource (lib "eagle-import") (part "R-US_0207/10"))
    )
  )
  (nets
    (net (code "1") (name "-15V") (class "Default")
      (node (ref "U$1") (pin "AB2") (pinfunction "1_AB2") (pintype "bidirectional"))
      (node (ref "U$1") (pin "BB2") (pinfunction "1_BB2") (pintype "bidirectional"))
      (node (ref "U$1") (pin "CB2") (pinfunction "1_CB2") (pintype "bidirectional"))
      (node (ref "U$1") (pin "DB2") (pinfunction "1_DB2") (pintype "bidirectional"))
    )
    (net (code "2") (name "A15U1") (class "Default")
      (node (ref "E13") (pin "10") (pinfunction "I1_10") (pintype "input"))
      (node (ref "E13") (pin "12") (pinfunction "I2_12") (pintype "input"))
      (node (ref "E13") (pin "2") (pinfunction "I1_2") (pintype "input"))
      (node (ref "E13") (pin "4") (pinfunction "I2_4") (pintype "input"))
      (node (ref "E13") (pin "5") (pinfunction "I3_5") (pintype "input"))
      (node (ref "E13") (pin "9") (pinfunction "I0_9") (pintype "input"))
      (node (ref "E2") (pin "1") (pinfunction "I0_1") (pintype "input"))
      (node (ref "E2") (pin "2") (pinfunction "I1_2") (pintype "input"))
      (node (ref "E2") (pin "4") (pinfunction "I2_4") (pintype "input"))
      (node (ref "R11") (pin "2") (pinfunction "2_2") (pintype "passive"))
      (node (ref "R12") (pin "1") (pinfunction "1_1") (pintype "passive"))
      (node (ref "U$1") (pin "AU2") (pinfunction "1_AU2") (pintype "bidirectional"))
    )
    (net (code "3") (name "A15V1") (class "Default")
      (node (ref "E2") (pin "10") (pinfunction "I1_10") (pintype "input"))
      (node (ref "E2") (pin "12") (pinfunction "I2_12") (pintype "input"))
      (node (ref "E2") (pin "9") (pinfunction "I0_9") (pintype "input"))
      (node (ref "E8") (pin "1") (pinfunction "I0_1") (pintype "input"))
      (node (ref "E8") (pin "10") (pinfunction "I1_10") (pintype "input"))
      (node (ref "E8") (pin "12") (pinfunction "I2_12") (pintype "input"))
      (node (ref "E8") (pin "2") (pinfunction "I1_2") (pintype "input"))
      (node (ref "E8") (pin "4") (pinfunction "I2_4") (pintype "input"))
      (node (ref "E8") (pin "9") (pinfunction "I0_9") (pintype "input"))
      (node (ref "R13") (pin "2") (pinfunction "2_2") (pintype "passive"))
      (node (ref "R14") (pin "1") (pinfunction "1_1") (pintype "passive"))
    )
    (net (code "4") (name "B17S1") (class "Default")
      (node (ref "E10") (pin "10") (pinfunction "PRE_10") (pintype "input"))
      (node (ref "E10") (pin "4") (pinfunction "PRE_4") (pintype "input"))
      (node (ref "E12") (pin "3") (pinfunction "O_3") (pintype "output"))
      (node (ref "E14") (pin "10") (pinfunction "PRE_10") (pintype "input"))
      (node (ref "E19") (pin "4") (pinfunction "PRE_4") (pintype "input"))
      (node (ref "E49") (pin "1") (pinfunction "I0_1") (pintype "input"))
      (node (ref "E49") (pin "4") (pinfunction "I0_4") (pintype "input"))
      (node (ref "E49") (pin "9") (pinfunction "I0_9") (pintype "input"))
    )
    (net (code "5") (name "B17V1") (class "Default")
      (node (ref "E10") (pin "1") (pinfunction "CLR_1") (pintype "input"))
      (node (ref "E10") (pin "13") (pinfunction "CLR_13") (pintype "input"))
      (node (ref "E14") (pin "13") (pinfunction "CLR_13") (pintype "input"))
      (node (ref "E26") (pin "1") (pinfunction "CLR_1") (pintype "input"))
      (node (ref "E26") (pin "13") (pinfunction "CLR_13") (pintype "input"))
      (node (ref "E27") (pin "1") (pinfunction "CLR_1") (pintype "input"))
      (node (ref "E27") (pin "13") (pinfunction "CLR_13") (pintype "input"))
      (node (ref "E52") (pin "1") (pinfunction "CLR_1") (pintype "input"))
      (node (ref "E52") (pin "13") (pinfunction "CLR_13") (pintype "input"))
      (node (ref "E53") (pin "1") (pinfunction "CLR_1") (pintype "input"))
      (node (ref "E53") (pin "13") (pinfunction "CLR_13") (pintype "input"))
      (node (ref "E6") (pin "1") (pinfunction "CLR_1") (pintype "input"))
      (node (ref "E6") (pin "13") (pinfunction "CLR_13") (pintype "input"))
      (node (ref "E7") (pin "3") (pinfunction "I0_3") (pintype "input"))
      (node (ref "E7") (pin "4") (pinfunction "I1_4") (pintype "input"))
      (node (ref "E9") (pin "1") (pinfunction "CLR_1") (pintype "input"))
      (node (ref "E9") (pin "13") (pinfunction "CLR_13") (pintype "input"))
      (node (ref "R15") (pin "2") (pinfunction "2_2") (pintype "passive"))
      (node (ref "R16") (pin "1") (pinfunction "1_1") (pintype "passive"))
    )
    (net (code "6") (name "C16U1") (class "Default")
      (node (ref "E18") (pin "10") (pinfunction "I1_10") (pintype "input"))
      (node (ref "E18") (pin "12") (pinfunction "I2_12") (pintype "input"))
      (node (ref "E18") (pin "13") (pinfunction "I3_13") (pintype "input"))
      (node (ref "E18") (pin "2") (pinfunction "I1_2") (pintype "input"))
      (node (ref "E18") (pin "4") (pinfunction "I2_4") (pintype "input"))
      (node (ref "E18") (pin "5") (pinfunction "I3_5") (pintype "input"))
      (node (ref "E22") (pin "2") (pinfunction "I1_2") (pintype "input"))
      (node (ref "E22") (pin "4") (pinfunction "I2_4") (pintype "input"))
      (node (ref "E22") (pin "5") (pinfunction "I3_5") (pintype "input"))
      (node (ref "R23") (pin "2") (pinfunction "2_2") (pintype "passive"))
      (node (ref "R24") (pin "1") (pinfunction "1_1") (pintype "passive"))
    )
    (net (code "7") (name "D01BINIT") (class "Default")
      (node (ref "E13") (pin "1") (pinfunction "I0_1") (pintype "input"))
      (node (ref "E18") (pin "1") (pinfunction "I0_1") (pintype "input"))
      (node (ref "E23") (pin "4") (pinfunction "O_4") (pintype "output"))
    )
    (net (code "8") (name "D01BTP2L") (class "Default")
      (node (ref "E20") (pin "4") (pinfunction "PRE_4") (pintype "input"))
      (node (ref "E23") (pin "2") (pinfunction "O_2") (pintype "output"))
      (node (ref "E7") (pin "13") (pinfunction "I2_13") (pintype "input"))
      (node (ref "E7") (pin "2") (pinfunction "I1_2") (pintype "input"))
    )
    (net (code "9") (name "D01DEL1H") (class "Default")
      (node (ref "E24") (pin "3") (pinfunction "I0_3") (pintype "input"))
      (node (ref "E44") (pin "8") (pinfunction "O_8") (pintype "output"))
      (node (ref "E7") (pin "5") (pinfunction "I2_5") (pintype "input"))
    )
    (net (code "10") (name "D01DEL1L") (class "Default")
      (node (ref "E14") (pin "4") (pinfunction "PRE_4") (pintype "input"))
      (node (ref "E15") (pin "4") (pinfunction "PRE_4") (pintype "input"))
      (node (ref "E7") (pin "6") (pinfunction "O_6") (pintype "output"))
    )
    (net (code "11") (name "D01DEL2") (class "Default")
      (node (ref "E24") (pin "1") (pinfunction "I0_1") (pintype "input"))
      (node (ref "E35") (pin "1") (pinfunction "IN_1") (pintype "input"))
      (node (ref "E44") (pin "6") (pinfunction "O_6") (pintype "output"))
      (node (ref "IC2") (pin "1") (pinfunction "IN_1") (pintype "input"))
    )
    (net (code "12") (name "D01DEL3") (class "Default")
      (node (ref "E15") (pin "11") (pinfunction "CLK_11") (pintype "input"))
      (node (ref "E15") (pin "3") (pinfunction "CLK_3") (pintype "input"))
      (node (ref "E36") (pin "8") (pinfunction "O_8") (pintype "output"))
    )
    (net (code "13") (name "D01DEL4") (class "Default")
      (node (ref "E14") (pin "3") (pinfunction "CLK_3") (pintype "input"))
      (node (ref "E16") (pin "3") (pinfunction "I0_3") (pintype "input"))
      (node (ref "E20") (pin "11") (pinfunction "CLK_11") (pintype "input"))
      (node (ref "E36") (pin "6") (pinfunction "O_6") (pintype "output"))
      (node (ref "E37") (pin "1") (pinfunction "I0_1") (pintype "input"))
      (node (ref "E7") (pin "9") (pinfunction "I0_9") (pintype "input"))
    )
    (net (code "14") (name "D01DEL5") (class "Default")
      (node (ref "E16") (pin "9") (pinfunction "I0_9") (pintype "input"))
      (node (ref "E20") (pin "3") (pinfunction "CLK_3") (pintype "input"))
      (node (ref "E40") (pin "6") (pinfunction "O_6") (pintype "output"))
    )
    (net (code "15") (name "D01DONEH") (class "Default")
      (node (ref "E23") (pin "8") (pinfunction "O_8") (pintype "output"))
      (node (ref "U$1") (pin "DS1") (pinfunction "1_DS1") (pintype "bidirectional"))
    )
    (net (code "16") (name "D01DONEL") (class "Default")
      (node (ref "E16") (pin "8") (pinfunction "O_8") (pintype "output"))
      (node (ref "E23") (pin "9") (pinfunction "I_9") (pintype "input"))
      (node (ref "E30") (pin "7") (pinfunction "I1_7") (pintype "input"))
    )
    (net (code "17") (name "D01INHIBIT") (class "Default")
      (node (ref "E8") (pin "8") (pinfunction "O_8") (pintype "output"))
      (node (ref "U$1") (pin "AP2") (pinfunction "1_AP2") (pintype "bidirectional"))
    )
    (net (code "18") (name "D01INITL") (class "Default")
      (node (ref "E13") (pin "6") (pinfunction "O_6") (pintype "output"))
      (node (ref "E14") (pin "1") (pinfunction "CLR_1") (pintype "input"))
      (node (ref "E15") (pin "1") (pinfunction "CLR_1") (pintype "input"))
      (node (ref "E15") (pin "13") (pinfunction "CLR_13") (pintype "input"))
      (node (ref "E19") (pin "1") (pinfunction "CLR_1") (pintype "input"))
      (node (ref "E19") (pin "13") (pinfunction "CLR_13") (pintype "input"))
      (node (ref "E20") (pin "1") (pinfunction "CLR_1") (pintype "input"))
      (node (ref "E20") (pin "13") (pinfunction "CLR_13") (pintype "input"))
    )
    (net (code "19") (name "D01LOADMDL") (class "Default")
      (node (ref "E16") (pin "6") (pinfunction "O_6") (pintype "output"))
      (node (ref "E49") (pin "10") (pinfunction "I1_10") (pintype "input"))
      (node (ref "E49") (pin "2") (pinfunction "I1_2") (pintype "input"))
      (node (ref "E49") (pin "5") (pinfunction "I1_5") (pintype "input"))
    )
    (net (code "20") (name "D01MEMDONEL") (class "Default")
      (node (ref "E30") (pin "5") (pinfunction "O_5") (pintype "open_collector"))
      (node (ref "H05/H24") (pin "28") (pinfunction "28_28") (pintype "passive"))
    )
    (net (code "21") (name "D01MEMSTARTL") (class "Default")
      (node (ref "E19") (pin "10") (pinfunction "PRE_10") (pintype "input"))
      (node (ref "E23") (pin "6") (pinfunction "O_6") (pintype "output"))
      (node (ref "E7") (pin "1") (pinfunction "I0_1") (pintype "input"))
    )
    (net (code "22") (name "D01POWEROK") (class "Default")
      (node (ref "E23") (pin "3") (pinfunction "I_3") (pintype "input"))
      (node (ref "U$1") (pin "BV2") (pinfunction "1_BV2") (pintype "bidirectional"))
    )
    (net (code "23") (name "D01READH") (class "Default")
      (node (ref "E16") (pin "4") (pinfunction "I1_4") (pintype "input"))
      (node (ref "E16") (pin "5") (pinfunction "I2_5") (pintype "input"))
      (node (ref "E19") (pin "9") (pinfunction "Q_9") (pintype "output"))
      (node (ref "E24") (pin "13") (pinfunction "I2_13") (pintype "input"))
      (node (ref "E24") (pin "2") (pinfunction "I1_2") (pintype "input"))
      (node (ref "E7") (pin "10") (pinfunction "I1_10") (pintype "input"))
      (node (ref "E7") (pin "11") (pinfunction "I2_11") (pintype "input"))
    )
    (net (code "24") (name "D01READL") (class "Default")
      (node (ref "E16") (pin "10") (pinfunction "I1_10") (pintype "input"))
      (node (ref "E16") (pin "11") (pinfunction "I2_11") (pintype "input"))
      (node (ref "E19") (pin "8") (pinfunction "~{Q}_8") (pintype "output"))
      (node (ref "U$1") (pin "AK2") (pinfunction "1_AK2") (pintype "bidirectional"))
    )
    (net (code "25") (name "D01RETURN") (class "Default")
      (node (ref "E13") (pin "8") (pinfunction "O_8") (pintype "output"))
      (node (ref "U$1") (pin "AR2") (pinfunction "1_AR2") (pintype "bidirectional"))
    )
    (net (code "26") (name "D01SELECTH") (class "Default")
      (node (ref "E18") (pin "9") (pinfunction "I0_9") (pintype "input"))
      (node (ref "E19") (pin "5") (pinfunction "Q_5") (pintype "output"))
    )
    (net (code "27") (name "D01SELECTL") (class "Default")
      (node (ref "E19") (pin "6") (pinfunction "~{Q}_6") (pintype "output"))
      (node (ref "E30") (pin "2") (pinfunction "I1_2") (pintype "input"))
      (node (ref "E30") (pin "6") (pinfunction "I0_6") (pintype "input"))
    )
    (net (code "28") (name "D01SELH") (class "Default")
      (node (ref "E11") (pin "6") (pinfunction "O_6") (pintype "output"))
      (node (ref "E19") (pin "2") (pinfunction "D_2") (pintype "input"))
    )
    (net (code "29") (name "D01SELL") (class "Default")
      (node (ref "E11") (pin "5") (pinfunction "I_5") (pintype "input"))
      (node (ref "E12") (pin "11") (pinfunction "O_11") (pintype "output"))
    )
    (net (code "30") (name "D01SOURCE") (class "Default")
      (node (ref "E2") (pin "6") (pinfunction "O_6") (pintype "output"))
      (node (ref "U$1") (pin "AL2") (pinfunction "1_AL2") (pintype "bidirectional"))
    )
    (net (code "31") (name "D01STROBE") (class "Default")
      (node (ref "E2") (pin "8") (pinfunction "O_8") (pintype "output"))
      (node (ref "U$1") (pin "AM2") (pinfunction "1_AM2") (pintype "bidirectional"))
    )
    (net (code "32") (name "D01STROBEL") (class "Default")
      (node (ref "E30") (pin "3") (pinfunction "O_3") (pintype "open_collector"))
      (node (ref "H05/H24") (pin "24") (pinfunction "24_24") (pintype "passive"))
      (node (ref "R17") (pin "2") (pinfunction "2_2") (pintype "passive"))
      (node (ref "R18") (pin "1") (pinfunction "1_1") (pintype "passive"))
    )
    (net (code "33") (name "D01WRITE") (class "Default")
      (node (ref "E8") (pin "6") (pinfunction "O_6") (pintype "output"))
      (node (ref "U$1") (pin "AS2") (pinfunction "1_AS2") (pintype "bidirectional"))
    )
    (net (code "34") (name "D01WRITEH") (class "Default")
      (node (ref "E20") (pin "5") (pinfunction "Q_5") (pintype "output"))
      (node (ref "E22") (pin "1") (pinfunction "I0_1") (pintype "input"))
      (node (ref "E24") (pin "4") (pinfunction "I1_4") (pintype "input"))
      (node (ref "E24") (pin "5") (pinfunction "I2_5") (pintype "input"))
    )
    (net (code "35") (name "D01WRITEL") (class "Default")
      (node (ref "E22") (pin "6") (pinfunction "O_6") (pintype "output"))
      (node (ref "E42") (pin "2") (pinfunction "I1_2") (pintype "input"))
      (node (ref "E42") (pin "7") (pinfunction "I1_7") (pintype "input"))
      (node (ref "E43") (pin "2") (pinfunction "I1_2") (pintype "input"))
      (node (ref "E43") (pin "7") (pinfunction "I1_7") (pintype "input"))
      (node (ref "E45") (pin "2") (pinfunction "I1_2") (pintype "input"))
      (node (ref "E45") (pin "7") (pinfunction "I1_7") (pintype "input"))
      (node (ref "E46") (pin "2") (pinfunction "I1_2") (pintype "input"))
      (node (ref "E46") (pin "7") (pinfunction "I1_7") (pintype "input"))
      (node (ref "E50") (pin "2") (pinfunction "I1_2") (pintype "input"))
      (node (ref "E50") (pin "7") (pinfunction "I1_7") (pintype "input"))
      (node (ref "E51") (pin "2") (pinfunction "I1_2") (pintype "input"))
      (node (ref "E51") (pin "7") (pinfunction "I1_7") (pintype "input"))
    )
    (net (code "36") (name "D02MEM0") (class "Default")
      (node (ref "E32") (pin "3") (pinfunction "O_3") (pintype "open_collector"))
      (node (ref "H04/H23") (pin "8") (pinfunction "8_8") (pintype "passive"))
    )
    (net (code "37") (name "D02MEM1") (class "Default")
      (node (ref "E32") (pin "5") (pinfunction "O_5") (pintype "open_collector"))
      (node (ref "H04/H23") (pin "12") (pinfunction "12_12") (pintype "passive"))
    )
    (net (code "38") (name "D02MEM2") (class "Default")
      (node (ref "E41") (pin "3") (pinfunction "O_3") (pintype "open_collector"))
      (node (ref "H04/H23") (pin "16") (pinfunction "16_16") (pintype "passive"))
    )
    (net (code "39") (name "D02MEM3") (class "Default")
      (node (ref "E41") (pin "5") (pinfunction "O_5") (pintype "open_collector"))
      (node (ref "H04/H23") (pin "20") (pinfunction "20_20") (pintype "passive"))
    )
    (net (code "40") (name "D02MEM4") (class "Default")
      (node (ref "E33") (pin "3") (pinfunction "O_3") (pintype "open_collector"))
      (node (ref "H04/H23") (pin "24") (pinfunction "24_24") (pintype "passive"))
    )
    (net (code "41") (name "D02MEM5") (class "Default")
      (node (ref "E33") (pin "5") (pinfunction "O_5") (pintype "open_collector"))
      (node (ref "H04/H23") (pin "28") (pinfunction "28_28") (pintype "passive"))
    )
    (net (code "42") (name "D02MEM6") (class "Default")
      (node (ref "E34") (pin "3") (pinfunction "O_3") (pintype "open_collector"))
      (node (ref "H04/H23") (pin "30") (pinfunction "30_30") (pintype "passive"))
    )
    (net (code "43") (name "D02MEM7") (class "Default")
      (node (ref "E34") (pin "5") (pinfunction "O_5") (pintype "open_collector"))
      (node (ref "H04/H23") (pin "32") (pinfunction "32_32") (pintype "passive"))
    )
    (net (code "44") (name "D02MEM8") (class "Default")
      (node (ref "E28") (pin "3") (pinfunction "O_3") (pintype "open_collector"))
      (node (ref "H05/H24") (pin "6") (pinfunction "6_6") (pintype "passive"))
    )
    (net (code "45") (name "D02MEM9") (class "Default")
      (node (ref "E28") (pin "5") (pinfunction "O_5") (pintype "open_collector"))
      (node (ref "H05/H24") (pin "8") (pinfunction "8_8") (pintype "passive"))
    )
    (net (code "46") (name "D02MEM10") (class "Default")
      (node (ref "E29") (pin "3") (pinfunction "O_3") (pintype "open_collector"))
      (node (ref "H05/H24") (pin "12") (pinfunction "12_12") (pintype "passive"))
    )
    (net (code "47") (name "D02MEM11") (class "Default")
      (node (ref "E29") (pin "5") (pinfunction "O_5") (pintype "open_collector"))
      (node (ref "H05/H24") (pin "16") (pinfunction "16_16") (pintype "passive"))
    )
    (net (code "48") (name "D03BEMA0L") (class "Default")
      (node (ref "E10") (pin "6") (pinfunction "~{Q}_6") (pintype "output"))
      (node (ref "U$1") (pin "AD2") (pinfunction "1_AD2") (pintype "bidirectional"))
    )
    (net (code "49") (name "D03BEMA1L") (class "Default")
      (node (ref "E10") (pin "8") (pinfunction "~{Q}_8") (pintype "output"))
      (node (ref "U$1") (pin "AE2") (pinfunction "1_AE2") (pintype "bidirectional"))
    )
    (net (code "50") (name "D03BEMA2L") (class "Default")
      (node (ref "E14") (pin "8") (pinfunction "~{Q}_8") (pintype "output"))
      (node (ref "U$1") (pin "AH2") (pinfunction "1_AH2") (pintype "bidirectional"))
    )
    (net (code "51") (name "D03BMA0") (class "Default")
      (node (ref "E1") (pin "9") (pinfunction "I0_9") (pintype "input"))
      (node (ref "H01/H20") (pin "16") (pinfunction "16_16") (pintype "passive"))
    )
    (net (code "52") (name "D03BMA1") (class "Default")
      (node (ref "E1") (pin "1") (pinfunction "I0_1") (pintype "input"))
      (node (ref "H01/H20") (pin "20") (pinfunction "20_20") (pintype "passive"))
    )
    (net (code "53") (name "D03BMA2") (class "Default")
      (node (ref "E5") (pin "9") (pinfunction "I0_9") (pintype "input"))
      (node (ref "H01/H20") (pin "24") (pinfunction "24_24") (pintype "passive"))
    )
    (net (code "54") (name "D03BMA3") (class "Default")
      (node (ref "E5") (pin "1") (pinfunction "I0_1") (pintype "input"))
      (node (ref "H01/H20") (pin "28") (pinfunction "28_28") (pintype "passive"))
    )
    (net (code "55") (name "D03BMA4") (class "Default")
      (node (ref "E17") (pin "9") (pinfunction "I0_9") (pintype "input"))
      (node (ref "H01/H20") (pin "30") (pinfunction "30_30") (pintype "passive"))
    )
    (net (code "56") (name "D03BMA5") (class "Default")
      (node (ref "E17") (pin "1") (pinfunction "I0_1") (pintype "input"))
      (node (ref "H01/H20") (pin "32") (pinfunction "32_32") (pintype "passive"))
    )
    (net (code "57") (name "D03BMA6") (class "Default")
      (node (ref "E21") (pin "9") (pinfunction "I0_9") (pintype "input"))
      (node (ref "H02/H21") (pin "6") (pinfunction "6_6") (pintype "passive"))
    )
    (net (code "58") (name "D03BMA7") (class "Default")
      (node (ref "E21") (pin "1") (pinfunction "I0_1") (pintype "input"))
      (node (ref "H02/H21") (pin "8") (pinfunction "8_8") (pintype "passive"))
    )
    (net (code "59") (name "D03BMA8") (class "Default")
      (node (ref "E47") (pin "9") (pinfunction "I0_9") (pintype "input"))
      (node (ref "H02/H21") (pin "12") (pinfunction "12_12") (pintype "passive"))
    )
    (net (code "60") (name "D03BMA9") (class "Default")
      (node (ref "E47") (pin "1") (pinfunction "I0_1") (pintype "input"))
      (node (ref "H02/H21") (pin "16") (pinfunction "16_16") (pintype "passive"))
    )
    (net (code "61") (name "D03BMA10") (class "Default")
      (node (ref "E48") (pin "9") (pinfunction "I0_9") (pintype "input"))
      (node (ref "H02/H21") (pin "20") (pinfunction "20_20") (pintype "passive"))
    )
    (net (code "62") (name "D03BMA11") (class "Default")
      (node (ref "E48") (pin "1") (pinfunction "I0_1") (pintype "input"))
      (node (ref "H02/H21") (pin "24") (pinfunction "24_24") (pintype "passive"))
    )
    (net (code "63") (name "D03BTP2") (class "Default")
      (node (ref "E19") (pin "11") (pinfunction "CLK_11") (pintype "input"))
      (node (ref "E23") (pin "1") (pinfunction "I_1") (pintype "input"))
      (node (ref "H05/H24") (pin "32") (pinfunction "32_32") (pintype "passive"))
    )
    (net (code "64") (name "D03EA0") (class "Default")
      (node (ref "E4") (pin "1") (pinfunction "I0_1") (pintype "input"))
      (node (ref "H03/H22") (pin "6") (pinfunction "6_6") (pintype "passive"))
    )
    (net (code "65") (name "D03EA1") (class "Default")
      (node (ref "E4") (pin "9") (pinfunction "I0_9") (pintype "input"))
      (node (ref "H03/H22") (pin "8") (pinfunction "8_8") (pintype "passive"))
    )
    (net (code "66") (name "D03EA2") (class "Default")
      (node (ref "E3") (pin "1") (pinfunction "I0_1") (pintype "input"))
      (node (ref "H03/H22") (pin "12") (pinfunction "12_12") (pintype "passive"))
    )
    (net (code "67") (name "D03EMA0H") (class "Default")
      (node (ref "E10") (pin "2") (pinfunction "D_2") (pintype "input"))
      (node (ref "E11") (pin "8") (pinfunction "O_8") (pintype "output"))
      (node (ref "E12") (pin "9") (pinfunction "I0_9") (pintype "input"))
      (node (ref "JP1") (pin "1") (pinfunction "1_1") (pintype "passive"))
    )
    (net (code "68") (name "D03EMA0L") (class "Default")
      (node (ref "E11") (pin "1") (pinfunction "I_1") (pintype "input"))
      (node (ref "E11") (pin "9") (pinfunction "I_9") (pintype "input"))
      (node (ref "E12") (pin "4") (pinfunction "I0_4") (pintype "input"))
      (node (ref "E4") (pin "6") (pinfunction "O_6") (pintype "output"))
      (node (ref "JP1") (pin "3") (pinfunction "3_3") (pintype "passive"))
    )
    (net (code "69") (name "D03EMA1H") (class "Default")
      (node (ref "E10") (pin "12") (pinfunction "D_12") (pintype "input"))
      (node (ref "E11") (pin "10") (pinfunction "O_10") (pintype "output"))
      (node (ref "E12") (pin "10") (pinfunction "I1_10") (pintype "input"))
      (node (ref "JP2") (pin "3") (pinfunction "3_3") (pintype "passive"))
    )
    (net (code "70") (name "D03EMA1L") (class "Default")
      (node (ref "E11") (pin "11") (pinfunction "I_11") (pintype "input"))
      (node (ref "E12") (pin "5") (pinfunction "I1_5") (pintype "input"))
      (node (ref "E4") (pin "8") (pinfunction "O_8") (pintype "output"))
      (node (ref "JP2") (pin "1") (pinfunction "1_1") (pintype "passive"))
    )
    (net (code "71") (name "D03EMA2H") (class "Default")
      (node (ref "E11") (pin "12") (pinfunction "O_12") (pintype "output"))
      (node (ref "E14") (pin "12") (pinfunction "D_12") (pintype "input"))
      (node (ref "JP3") (pin "1") (pinfunction "1_1") (pintype "passive"))
    )
    (net (code "72") (name "D03EMA2L") (class "Default")
      (node (ref "E11") (pin "13") (pinfunction "I_13") (pintype "input"))
      (node (ref "E3") (pin "6") (pinfunction "O_6") (pintype "output"))
      (node (ref "JP3") (pin "3") (pinfunction "3_3") (pintype "passive"))
    )
    (net (code "73") (name "D03MA0L") (class "Default")
      (node (ref "E1") (pin "8") (pinfunction "O_8") (pintype "output"))
      (node (ref "U$1") (pin "AD1") (pinfunction "1_AD1") (pintype "bidirectional"))
    )
    (net (code "74") (name "D03MA1L") (class "Default")
      (node (ref "E1") (pin "6") (pinfunction "O_6") (pintype "output"))
      (node (ref "U$1") (pin "AE1") (pinfunction "1_AE1") (pintype "bidirectional"))
    )
    (net (code "75") (name "D03MA2L") (class "Default")
      (node (ref "E5") (pin "8") (pinfunction "O_8") (pintype "output"))
      (node (ref "U$1") (pin "AH1") (pinfunction "1_AH1") (pintype "bidirectional"))
    )
    (net (code "76") (name "D03MA3L") (class "Default")
      (node (ref "E5") (pin "6") (pinfunction "O_6") (pintype "output"))
      (node (ref "U$1") (pin "AJ1") (pinfunction "1_AJ1") (pintype "bidirectional"))
    )
    (net (code "77") (name "D03MA4L") (class "Default")
      (node (ref "E17") (pin "8") (pinfunction "O_8") (pintype "output"))
      (node (ref "U$1") (pin "BD1") (pinfunction "1_BD1") (pintype "bidirectional"))
    )
    (net (code "78") (name "D03MA5L") (class "Default")
      (node (ref "E17") (pin "6") (pinfunction "O_6") (pintype "output"))
      (node (ref "U$1") (pin "BE1") (pinfunction "1_BE1") (pintype "bidirectional"))
    )
    (net (code "79") (name "D03MA6L") (class "Default")
      (node (ref "E21") (pin "8") (pinfunction "O_8") (pintype "output"))
      (node (ref "U$1") (pin "BH1") (pinfunction "1_BH1") (pintype "bidirectional"))
    )
    (net (code "80") (name "D03MA7L") (class "Default")
      (node (ref "E21") (pin "6") (pinfunction "O_6") (pintype "output"))
      (node (ref "U$1") (pin "BJ1") (pinfunction "1_BJ1") (pintype "bidirectional"))
    )
    (net (code "81") (name "D03MA8L") (class "Default")
      (node (ref "E47") (pin "8") (pinfunction "O_8") (pintype "output"))
      (node (ref "U$1") (pin "DD1") (pinfunction "1_DD1") (pintype "bidirectional"))
    )
    (net (code "82") (name "D03MA9L") (class "Default")
      (node (ref "E47") (pin "6") (pinfunction "O_6") (pintype "output"))
      (node (ref "U$1") (pin "DE1") (pinfunction "1_DE1") (pintype "bidirectional"))
    )
    (net (code "83") (name "D03MA10L") (class "Default")
      (node (ref "E48") (pin "8") (pinfunction "O_8") (pintype "output"))
      (node (ref "U$1") (pin "DH1") (pinfunction "1_DH1") (pintype "bidirectional"))
    )
    (net (code "84") (name "D03MA11L") (class "Default")
      (node (ref "E48") (pin "6") (pinfunction "O_6") (pintype "output"))
      (node (ref "U$1") (pin "DJ1") (pinfunction "1_DJ1") (pintype "bidirectional"))
    )
    (net (code "85") (name "D03MCBMB0L") (class "Default")
      (node (ref "E46") (pin "1") (pinfunction "I0_1") (pintype "input"))
      (node (ref "H02/H21") (pin "28") (pinfunction "28_28") (pintype "passive"))
    )
    (net (code "86") (name "D03MCBMB1L") (class "Default")
      (node (ref "E46") (pin "6") (pinfunction "I0_6") (pintype "input"))
      (node (ref "H02/H21") (pin "30") (pinfunction "30_30") (pintype "passive"))
    )
    (net (code "87") (name "D03MCBMB2L") (class "Default")
      (node (ref "E51") (pin "6") (pinfunction "I0_6") (pintype "input"))
      (node (ref "H02/H21") (pin "32") (pinfunction "32_32") (pintype "passive"))
    )
    (net (code "88") (name "D03MCBMB3L") (class "Default")
      (node (ref "E50") (pin "1") (pinfunction "I0_1") (pintype "input"))
      (node (ref "H01/H20") (pin "6") (pinfunction "6_6") (pintype "passive"))
    )
    (net (code "89") (name "D03MCBMB4L") (class "Default")
      (node (ref "E50") (pin "6") (pinfunction "I0_6") (pintype "input"))
      (node (ref "H01/H20") (pin "8") (pinfunction "8_8") (pintype "passive"))
    )
    (net (code "90") (name "D03MCBMB5L") (class "Default")
      (node (ref "E51") (pin "1") (pinfunction "I0_1") (pintype "input"))
      (node (ref "H01/H20") (pin "12") (pinfunction "12_12") (pintype "passive"))
    )
    (net (code "91") (name "D03MCBMB6L") (class "Default")
      (node (ref "E45") (pin "1") (pinfunction "I0_1") (pintype "input"))
      (node (ref "H03/H22") (pin "16") (pinfunction "16_16") (pintype "passive"))
    )
    (net (code "92") (name "D03MCBMB7L") (class "Default")
      (node (ref "E45") (pin "6") (pinfunction "I0_6") (pintype "input"))
      (node (ref "H03/H22") (pin "20") (pinfunction "20_20") (pintype "passive"))
    )
    (net (code "93") (name "D03MCBMB8L") (class "Default")
      (node (ref "E42") (pin "1") (pinfunction "I0_1") (pintype "input"))
      (node (ref "H03/H22") (pin "24") (pinfunction "24_24") (pintype "passive"))
    )
    (net (code "94") (name "D03MCBMB9L") (class "Default")
      (node (ref "E42") (pin "6") (pinfunction "I0_6") (pintype "input"))
      (node (ref "H03/H22") (pin "28") (pinfunction "28_28") (pintype "passive"))
    )
    (net (code "95") (name "D03MCBMB10L") (class "Default")
      (node (ref "E43") (pin "1") (pinfunction "I0_1") (pintype "input"))
      (node (ref "H03/H22") (pin "30") (pinfunction "30_30") (pintype "passive"))
    )
    (net (code "96") (name "D03MCBMB11L") (class "Default")
      (node (ref "E43") (pin "6") (pinfunction "I0_6") (pintype "input"))
      (node (ref "H03/H22") (pin "32") (pinfunction "32_32") (pintype "passive"))
    )
    (net (code "97") (name "D03MEMSTART") (class "Default")
      (node (ref "E10") (pin "11") (pinfunction "CLK_11") (pintype "input"))
      (node (ref "E10") (pin "3") (pinfunction "CLK_3") (pintype "input"))
      (node (ref "E14") (pin "11") (pinfunction "CLK_11") (pintype "input"))
      (node (ref "E19") (pin "3") (pinfunction "CLK_3") (pintype "input"))
      (node (ref "E23") (pin "5") (pinfunction "I_5") (pintype "input"))
      (node (ref "H05/H24") (pin "20") (pinfunction "20_20") (pintype "passive"))
    )
    (net (code "98") (name "D04MD0L") (class "Default")
      (node (ref "E46") (pin "3") (pinfunction "O_3") (pintype "open_collector"))
      (node (ref "E6") (pin "12") (pinfunction "D_12") (pintype "input"))
      (node (ref "U$1") (pin "AK1") (pinfunction "1_AK1") (pintype "bidirectional"))
    )
    (net (code "99") (name "D04MD1L") (class "Default")
      (node (ref "E46") (pin "5") (pinfunction "O_5") (pintype "open_collector"))
      (node (ref "E6") (pin "2") (pinfunction "D_2") (pintype "input"))
      (node (ref "U$1") (pin "AL1") (pinfunction "1_AL1") (pintype "bidirectional"))
    )
    (net (code "100") (name "D04MD2L") (class "Default")
      (node (ref "E51") (pin "5") (pinfunction "O_5") (pintype "open_collector"))
      (node (ref "E9") (pin "12") (pinfunction "D_12") (pintype "input"))
      (node (ref "U$1") (pin "AM1") (pinfunction "1_AM1") (pintype "bidirectional"))
    )
    (net (code "101") (name "D04MD3L") (class "Default")
      (node (ref "E50") (pin "3") (pinfunction "O_3") (pintype "open_collector"))
      (node (ref "E9") (pin "2") (pinfunction "D_2") (pintype "input"))
      (node (ref "U$1") (pin "AP1") (pinfunction "1_AP1") (pintype "bidirectional"))
    )
    (net (code "102") (name "D04MD4L") (class "Default")
      (node (ref "E26") (pin "12") (pinfunction "D_12") (pintype "input"))
      (node (ref "E50") (pin "5") (pinfunction "O_5") (pintype "open_collector"))
      (node (ref "U$1") (pin "BK1") (pinfunction "1_BK1") (pintype "bidirectional"))
    )
    (net (code "103") (name "D04MD5L") (class "Default")
      (node (ref "E26") (pin "2") (pinfunction "D_2") (pintype "input"))
      (node (ref "E51") (pin "3") (pinfunction "O_3") (pintype "open_collector"))
      (node (ref "U$1") (pin "BL1") (pinfunction "1_BL1") (pintype "bidirectional"))
    )
    (net (code "104") (name "D04MD6L") (class "Default")
      (node (ref "E27") (pin "12") (pinfunction "D_12") (pintype "input"))
      (node (ref "E45") (pin "3") (pinfunction "O_3") (pintype "open_collector"))
      (node (ref "U$1") (pin "BM1") (pinfunction "1_BM1") (pintype "bidirectional"))
    )
    (net (code "105") (name "D04MD7L") (class "Default")
      (node (ref "E27") (pin "2") (pinfunction "D_2") (pintype "input"))
      (node (ref "E45") (pin "5") (pinfunction "O_5") (pintype "open_collector"))
      (node (ref "U$1") (pin "BP1") (pinfunction "1_BP1") (pintype "bidirectional"))
    )
    (net (code "106") (name "D04MD8L") (class "Default")
      (node (ref "E42") (pin "3") (pinfunction "O_3") (pintype "open_collector"))
      (node (ref "E53") (pin "12") (pinfunction "D_12") (pintype "input"))
      (node (ref "U$1") (pin "DK1") (pinfunction "1_DK1") (pintype "bidirectional"))
    )
    (net (code "107") (name "D04MD9L") (class "Default")
      (node (ref "E42") (pin "5") (pinfunction "O_5") (pintype "open_collector"))
      (node (ref "E53") (pin "2") (pinfunction "D_2") (pintype "input"))
      (node (ref "U$1") (pin "DL1") (pinfunction "1_DL1") (pintype "bidirectional"))
    )
    (net (code "108") (name "D04MD10L") (class "Default")
      (node (ref "E43") (pin "3") (pinfunction "O_3") (pintype "open_collector"))
      (node (ref "E52") (pin "12") (pinfunction "D_12") (pintype "input"))
      (node (ref "U$1") (pin "DM1") (pinfunction "1_DM1") (pintype "bidirectional"))
    )
    (net (code "109") (name "D04MD11L") (class "Default")
      (node (ref "E43") (pin "5") (pinfunction "O_5") (pintype "open_collector"))
      (node (ref "E52") (pin "2") (pinfunction "D_2") (pintype "input"))
      (node (ref "U$1") (pin "DP1") (pinfunction "1_DP1") (pintype "bidirectional"))
    )
    (net (code "110") (name "GND") (class "Default")
      (node (ref "D1") (pin "A") (pinfunction "A_A") (pintype "passive"))
      (node (ref "D2") (pin "A") (pinfunction "A_A") (pintype "passive"))
      (node (ref "D3") (pin "A") (pinfunction "A_A") (pintype "passive"))
      (node (ref "D4") (pin "A") (pinfunction "A_A") (pintype "passive"))
      (node (ref "D5") (pin "A") (pinfunction "A_A") (pintype "passive"))
      (node (ref "E12") (pin "1") (pinfunction "I0_1") (pintype "input"))
      (node (ref "E12") (pin "2") (pinfunction "I1_2") (pintype "input"))
      (node (ref "E14") (pin "2") (pinfunction "D_2") (pintype "input"))
      (node (ref "E15") (pin "12") (pinfunction "D_12") (pintype "input"))
      (node (ref "E15") (pin "2") (pinfunction "D_2") (pintype "input"))
      (node (ref "E19") (pin "12") (pinfunction "D_12") (pintype "input"))
      (node (ref "E20") (pin "12") (pinfunction "D_12") (pintype "input"))
      (node (ref "E20") (pin "2") (pinfunction "D_2") (pintype "input"))
      (node (ref "H01/H20") (pin "1") (pinfunction "1_1") (pintype "passive"))
      (node (ref "H01/H20") (pin "11") (pinfunction "11_11") (pintype "passive"))
      (node (ref "H01/H20") (pin "13") (pinfunction "13_13") (pintype "passive"))
      (node (ref "H01/H20") (pin "15") (pinfunction "15_15") (pintype "passive"))
      (node (ref "H01/H20") (pin "17") (pinfunction "17_17") (pintype "passive"))
      (node (ref "H01/H20") (pin "19") (pinfunction "19_19") (pintype "passive"))
      (node (ref "H01/H20") (pin "21") (pinfunction "21_21") (pintype "passive"))
      (node (ref "H01/H20") (pin "23") (pinfunction "23_23") (pintype "passive"))
      (node (ref "H01/H20") (pin "25") (pinfunction "25_25") (pintype "passive"))
      (node (ref "H01/H20") (pin "27") (pinfunction "27_27") (pintype "passive"))
      (node (ref "H01/H20") (pin "29") (pinfunction "29_29") (pintype "passive"))
      (node (ref "H01/H20") (pin "3") (pinfunction "3_3") (pintype "passive"))
      (node (ref "H01/H20") (pin "31") (pinfunction "31_31") (pintype "passive"))
      (node (ref "H01/H20") (pin "33") (pinfunction "33_33") (pintype "passive"))
      (node (ref "H01/H20") (pin "5") (pinfunction "5_5") (pintype "passive"))
      (node (ref "H01/H20") (pin "7") (pinfunction "7_7") (pintype "passive"))
      (node (ref "H01/H20") (pin "9") (pinfunction "9_9") (pintype "passive"))
      (node (ref "H02/H21") (pin "1") (pinfunction "1_1") (pintype "passive"))
      (node (ref "H02/H21") (pin "11") (pinfunction "11_11") (pintype "passive"))
      (node (ref "H02/H21") (pin "13") (pinfunction "13_13") (pintype "passive"))
      (node (ref "H02/H21") (pin "15") (pinfunction "15_15") (pintype "passive"))
      (node (ref "H02/H21") (pin "17") (pinfunction "17_17") (pintype "passive"))
      (node (ref "H02/H21") (pin "19") (pinfunction "19_19") (pintype "passive"))
      (node (ref "H02/H21") (pin "21") (pinfunction "21_21") (pintype "passive"))
      (node (ref "H02/H21") (pin "23") (pinfunction "23_23") (pintype "passive"))
      (node (ref "H02/H21") (pin "25") (pinfunction "25_25") (pintype "passive"))
      (node (ref "H02/H21") (pin "27") (pinfunction "27_27") (pintype "passive"))
      (node (ref "H02/H21") (pin "29") (pinfunction "29_29") (pintype "passive"))
      (node (ref "H02/H21") (pin "3") (pinfunction "3_3") (pintype "passive"))
      (node (ref "H02/H21") (pin "31") (pinfunction "31_31") (pintype "passive"))
      (node (ref "H02/H21") (pin "33") (pinfunction "33_33") (pintype "passive"))
      (node (ref "H02/H21") (pin "5") (pinfunction "5_5") (pintype "passive"))
      (node (ref "H02/H21") (pin "7") (pinfunction "7_7") (pintype "passive"))
      (node (ref "H02/H21") (pin "9") (pinfunction "9_9") (pintype "passive"))
      (node (ref "H03/H22") (pin "1") (pinfunction "1_1") (pintype "passive"))
      (node (ref "H03/H22") (pin "11") (pinfunction "11_11") (pintype "passive"))
      (node (ref "H03/H22") (pin "13") (pinfunction "13_13") (pintype "passive"))
      (node (ref "H03/H22") (pin "15") (pinfunction "15_15") (pintype "passive"))
      (node (ref "H03/H22") (pin "17") (pinfunction "17_17") (pintype "passive"))
      (node (ref "H03/H22") (pin "19") (pinfunction "19_19") (pintype "passive"))
      (node (ref "H03/H22") (pin "21") (pinfunction "21_21") (pintype "passive"))
      (node (ref "H03/H22") (pin "23") (pinfunction "23_23") (pintype "passive"))
      (node (ref "H03/H22") (pin "25") (pinfunction "25_25") (pintype "passive"))
      (node (ref "H03/H22") (pin "27") (pinfunction "27_27") (pintype "passive"))
      (node (ref "H03/H22") (pin "29") (pinfunction "29_29") (pintype "passive"))
      (node (ref "H03/H22") (pin "3") (pinfunction "3_3") (pintype "passive"))
      (node (ref "H03/H22") (pin "31") (pinfunction "31_31") (pintype "passive"))
      (node (ref "H03/H22") (pin "33") (pinfunction "33_33") (pintype "passive"))
      (node (ref "H03/H22") (pin "5") (pinfunction "5_5") (pintype "passive"))
      (node (ref "H03/H22") (pin "7") (pinfunction "7_7") (pintype "passive"))
      (node (ref "H03/H22") (pin "9") (pinfunction "9_9") (pintype "passive"))
      (node (ref "H04/H23") (pin "1") (pinfunction "1_1") (pintype "passive"))
      (node (ref "H04/H23") (pin "11") (pinfunction "11_11") (pintype "passive"))
      (node (ref "H04/H23") (pin "13") (pinfunction "13_13") (pintype "passive"))
      (node (ref "H04/H23") (pin "15") (pinfunction "15_15") (pintype "passive"))
      (node (ref "H04/H23") (pin "17") (pinfunction "17_17") (pintype "passive"))
      (node (ref "H04/H23") (pin "19") (pinfunction "19_19") (pintype "passive"))
      (node (ref "H04/H23") (pin "21") (pinfunction "21_21") (pintype "passive"))
      (node (ref "H04/H23") (pin "23") (pinfunction "23_23") (pintype "passive"))
      (node (ref "H04/H23") (pin "25") (pinfunction "25_25") (pintype "passive"))
      (node (ref "H04/H23") (pin "27") (pinfunction "27_27") (pintype "passive"))
      (node (ref "H04/H23") (pin "29") (pinfunction "29_29") (pintype "passive"))
      (node (ref "H04/H23") (pin "3") (pinfunction "3_3") (pintype "passive"))
      (node (ref "H04/H23") (pin "31") (pinfunction "31_31") (pintype "passive"))
      (node (ref "H04/H23") (pin "33") (pinfunction "33_33") (pintype "passive"))
      (node (ref "H04/H23") (pin "5") (pinfunction "5_5") (pintype "passive"))
      (node (ref "H04/H23") (pin "7") (pinfunction "7_7") (pintype "passive"))
      (node (ref "H04/H23") (pin "9") (pinfunction "9_9") (pintype "passive"))
      (node (ref "H05/H24") (pin "1") (pinfunction "1_1") (pintype "passive"))
      (node (ref "H05/H24") (pin "11") (pinfunction "11_11") (pintype "passive"))
      (node (ref "H05/H24") (pin "13") (pinfunction "13_13") (pintype "passive"))
      (node (ref "H05/H24") (pin "15") (pinfunction "15_15") (pintype "passive"))
      (node (ref "H05/H24") (pin "17") (pinfunction "17_17") (pintype "passive"))
      (node (ref "H05/H24") (pin "19") (pinfunction "19_19") (pintype "passive"))
      (node (ref "H05/H24") (pin "21") (pinfunction "21_21") (pintype "passive"))
      (node (ref "H05/H24") (pin "23") (pinfunction "23_23") (pintype "passive"))
      (node (ref "H05/H24") (pin "25") (pinfunction "25_25") (pintype "passive"))
      (node (ref "H05/H24") (pin "27") (pinfunction "27_27") (pintype "passive"))
      (node (ref "H05/H24") (pin "29") (pinfunction "29_29") (pintype "passive"))
      (node (ref "H05/H24") (pin "3") (pinfunction "3_3") (pintype "passive"))
      (node (ref "H05/H24") (pin "31") (pinfunction "31_31") (pintype "passive"))
      (node (ref "H05/H24") (pin "33") (pinfunction "33_33") (pintype "passive"))
      (node (ref "H05/H24") (pin "5") (pinfunction "5_5") (pintype "passive"))
      (node (ref "H05/H24") (pin "7") (pinfunction "7_7") (pintype "passive"))
      (node (ref "H05/H24") (pin "9") (pinfunction "9_9") (pintype "passive"))
      (node (ref "JP2") (pin "5") (pinfunction "5_5") (pintype "passive"))
      (node (ref "R10") (pin "2") (pinfunction "2_2") (pintype "passive"))
      (node (ref "R12") (pin "2") (pinfunction "2_2") (pintype "passive"))
      (node (ref "R14") (pin "2") (pinfunction "2_2") (pintype "passive"))
      (node (ref "R16") (pin "2") (pinfunction "2_2") (pintype "passive"))
      (node (ref "R18") (pin "2") (pinfunction "2_2") (pintype "passive"))
      (node (ref "R19") (pin "1") (pinfunction "1_1") (pintype "passive"))
      (node (ref "R2") (pin "2") (pinfunction "2_2") (pintype "passive"))
      (node (ref "R21") (pin "1") (pinfunction "1_1") (pintype "passive"))
      (node (ref "R24") (pin "2") (pinfunction "2_2") (pintype "passive"))
      (node (ref "R25") (pin "1") (pinfunction "1_1") (pintype "passive"))
      (node (ref "R27") (pin "1") (pinfunction "1_1") (pintype "passive"))
      (node (ref "R29") (pin "1") (pinfunction "1_1") (pintype "passive"))
      (node (ref "R4") (pin "2") (pinfunction "2_2") (pintype "passive"))
      (node (ref "R6") (pin "2") (pinfunction "2_2") (pintype "passive"))
      (node (ref "R7") (pin "2") (pinfunction "2_2") (pintype "passive"))
      (node (ref "U$1") (pin "AC1") (pinfunction "1_AC1") (pintype "bidirectional"))
      (node (ref "U$1") (pin "AC2") (pinfunction "1_AC2") (pintype "bidirectional"))
      (node (ref "U$1") (pin "AF1") (pinfunction "1_AF1") (pintype "bidirectional"))
      (node (ref "U$1") (pin "AF2") (pinfunction "1_AF2") (pintype "bidirectional"))
      (node (ref "U$1") (pin "AN1") (pinfunction "1_AN1") (pintype "bidirectional"))
      (node (ref "U$1") (pin "AN2") (pinfunction "1_AN2") (pintype "bidirectional"))
      (node (ref "U$1") (pin "AT1") (pinfunction "1_AT1") (pintype "bidirectional"))
      (node (ref "U$1") (pin "AT2") (pinfunction "1_AT2") (pintype "bidirectional"))
      (node (ref "U$1") (pin "BC1") (pinfunction "1_BC1") (pintype "bidirectional"))
      (node (ref "U$1") (pin "BC2") (pinfunction "1_BC2") (pintype "bidirectional"))
      (node (ref "U$1") (pin "BF1") (pinfunction "1_BF1") (pintype "bidirectional"))
      (node (ref "U$1") (pin "BF2") (pinfunction "1_BF2") (pintype "bidirectional"))
      (node (ref "U$1") (pin "BN1") (pinfunction "1_BN1") (pintype "bidirectional"))
      (node (ref "U$1") (pin "BN2") (pinfunction "1_BN2") (pintype "bidirectional"))
      (node (ref "U$1") (pin "BT1") (pinfunction "1_BT1") (pintype "bidirectional"))
      (node (ref "U$1") (pin "BT2") (pinfunction "1_BT2") (pintype "bidirectional"))
      (node (ref "U$1") (pin "CC1") (pinfunction "1_CC1") (pintype "bidirectional"))
      (node (ref "U$1") (pin "CC2") (pinfunction "1_CC2") (pintype "bidirectional"))
      (node (ref "U$1") (pin "CF1") (pinfunction "1_CF1") (pintype "bidirectional"))
      (node (ref "U$1") (pin "CF2") (pinfunction "1_CF2") (pintype "bidirectional"))
      (node (ref "U$1") (pin "CN1") (pinfunction "1_CN1") (pintype "bidirectional"))
      (node (ref "U$1") (pin "CN2") (pinfunction "1_CN2") (pintype "bidirectional"))
      (node (ref "U$1") (pin "CT1") (pinfunction "1_CT1") (pintype "bidirectional"))
      (node (ref "U$1") (pin "CT2") (pinfunction "1_CT2") (pintype "bidirectional"))
      (node (ref "U$1") (pin "DC1") (pinfunction "1_DC1") (pintype "bidirectional"))
      (node (ref "U$1") (pin "DC2") (pinfunction "1_DC2") (pintype "bidirectional"))
      (node (ref "U$1") (pin "DF1") (pinfunction "1_DF1") (pintype "bidirectional"))
      (node (ref "U$1") (pin "DF2") (pinfunction "1_DF2") (pintype "bidirectional"))
      (node (ref "U$1") (pin "DN1") (pinfunction "1_DN1") (pintype "bidirectional"))
      (node (ref "U$1") (pin "DN2") (pinfunction "1_DN2") (pintype "bidirectional"))
      (node (ref "U$1") (pin "DT1") (pinfunction "1_DT1") (pintype "bidirectional"))
      (node (ref "U$1") (pin "DT2") (pinfunction "1_DT2") (pintype "bidirectional"))
    )
    (net (code "111") (name "Net-(E1A-I1)") (class "Default")
      (node (ref "E1") (pin "10") (pinfunction "I1_10") (pintype "input"))
      (node (ref "E1") (pin "12") (pinfunction "I2_12") (pintype "input"))
      (node (ref "E1") (pin "13") (pinfunction "I3_13") (pintype "input"))
      (node (ref "E1") (pin "2") (pinfunction "I1_2") (pintype "input"))
      (node (ref "E1") (pin "4") (pinfunction "I2_4") (pintype "input"))
      (node (ref "E1") (pin "5") (pinfunction "I3_5") (pintype "input"))
      (node (ref "E5") (pin "10") (pinfunction "I1_10") (pintype "input"))
      (node (ref "E5") (pin "12") (pinfunction "I2_12") (pintype "input"))
      (node (ref "E5") (pin "13") (pinfunction "I3_13") (pintype "input"))
      (node (ref "R3") (pin "2") (pinfunction "2_2") (pintype "passive"))
      (node (ref "R4") (pin "1") (pinfunction "1_1") (pintype "passive"))
    )
    (net (code "112") (name "Net-(E3A-I1)") (class "Default")
      (node (ref "E3") (pin "2") (pinfunction "I1_2") (pintype "input"))
      (node (ref "E3") (pin "4") (pinfunction "I2_4") (pintype "input"))
      (node (ref "E3") (pin "5") (pinfunction "I3_5") (pintype "input"))
      (node (ref "E4") (pin "10") (pinfunction "I1_10") (pintype "input"))
      (node (ref "E4") (pin "12") (pinfunction "I2_12") (pintype "input"))
      (node (ref "E4") (pin "13") (pinfunction "I3_13") (pintype "input"))
      (node (ref "E4") (pin "2") (pinfunction "I1_2") (pintype "input"))
      (node (ref "E4") (pin "4") (pinfunction "I2_4") (pintype "input"))
      (node (ref "E4") (pin "5") (pinfunction "I3_5") (pintype "input"))
      (node (ref "R1") (pin "2") (pinfunction "2_2") (pintype "passive"))
      (node (ref "R2") (pin "1") (pinfunction "1_1") (pintype "passive"))
    )
    (net (code "113") (name "Net-(E3B-I0)") (class "Default")
      (node (ref "E3") (pin "9") (pinfunction "I0_9") (pintype "input"))
      (node (ref "PAD1") (pin "1") (pinfunction "P_1") (pintype "passive"))
    )
    (net (code "114") (name "Net-(E3B-I1)") (class "Default")
      (node (ref "E3") (pin "10") (pinfunction "I1_10") (pintype "input"))
      (node (ref "PAD2") (pin "1") (pinfunction "P_1") (pintype "passive"))
    )
    (net (code "115") (name "Net-(E3B-I2)") (class "Default")
      (node (ref "E3") (pin "12") (pinfunction "I2_12") (pintype "input"))
      (node (ref "PAD3") (pin "1") (pinfunction "P_1") (pintype "passive"))
    )
    (net (code "116") (name "Net-(E3B-I3)") (class "Default")
      (node (ref "E3") (pin "13") (pinfunction "I3_13") (pintype "input"))
      (node (ref "PAD4") (pin "1") (pinfunction "P_1") (pintype "passive"))
    )
    (net (code "117") (name "Net-(E3B-O)") (class "Default")
      (node (ref "E3") (pin "8") (pinfunction "O_8") (pintype "output"))
      (node (ref "PAD5") (pin "1") (pinfunction "P_1") (pintype "passive"))
    )
    (net (code "118") (name "Net-(E11A-O)") (class "Default")
      (node (ref "E11") (pin "2") (pinfunction "O_2") (pintype "output"))
      (node (ref "JP4") (pin "3") (pinfunction "3_3") (pintype "passive"))
    )
    (net (code "119") (name "Net-(E11B-I)") (class "Default")
      (node (ref "E11") (pin "3") (pinfunction "I_3") (pintype "input"))
      (node (ref "E12") (pin "8") (pinfunction "O_8") (pintype "output"))
    )
    (net (code "120") (name "Net-(E11B-O)") (class "Default")
      (node (ref "E11") (pin "4") (pinfunction "O_4") (pintype "output"))
      (node (ref "JP4") (pin "5") (pinfunction "5_5") (pintype "passive"))
    )
    (net (code "121") (name "Net-(E12B-O)") (class "Default")
      (node (ref "E12") (pin "6") (pinfunction "O_6") (pintype "output"))
      (node (ref "JP4") (pin "1") (pinfunction "1_1") (pintype "passive"))
    )
    (net (code "122") (name "Net-(E12D-I0)") (class "Default")
      (node (ref "E12") (pin "12") (pinfunction "I0_12") (pintype "input"))
      (node (ref "E16") (pin "12") (pinfunction "O_12") (pintype "output"))
    )
    (net (code "123") (name "Net-(E12D-I1)") (class "Default")
      (node (ref "E12") (pin "13") (pinfunction "I1_13") (pintype "input"))
      (node (ref "JP4") (pin "2") (pinfunction "2_2") (pintype "passive"))
      (node (ref "JP4") (pin "4") (pinfunction "4_4") (pintype "passive"))
      (node (ref "JP4") (pin "6") (pinfunction "6_6") (pintype "passive"))
    )
    (net (code "124") (name "Net-(E13B-I3)") (class "Default")
      (node (ref "E13") (pin "13") (pinfunction "I3_13") (pintype "input"))
      (node (ref "E14") (pin "6") (pinfunction "~{Q}_6") (pintype "output"))
    )
    (net (code "125") (name "Net-(E15A-~{Q})") (class "Default")
      (node (ref "E15") (pin "6") (pinfunction "~{Q}_6") (pintype "output"))
      (node (ref "E2") (pin "5") (pinfunction "I3_5") (pintype "input"))
    )
    (net (code "126") (name "Net-(E15B-PRE)") (class "Default")
      (node (ref "E15") (pin "10") (pinfunction "PRE_10") (pintype "input"))
      (node (ref "E24") (pin "12") (pinfunction "O_12") (pintype "output"))
    )
    (net (code "127") (name "Net-(E15B-~{Q})") (class "Default")
      (node (ref "E15") (pin "8") (pinfunction "~{Q}_8") (pintype "output"))
      (node (ref "E2") (pin "13") (pinfunction "I3_13") (pintype "input"))
    )
    (net (code "128") (name "Net-(E16A-I0)") (class "Default")
      (node (ref "E16") (pin "1") (pinfunction "I0_1") (pintype "input"))
      (node (ref "JP1") (pin "2") (pinfunction "2_2") (pintype "passive"))
      (node (ref "JP1") (pin "4") (pinfunction "4_4") (pintype "passive"))
    )
    (net (code "129") (name "Net-(E16A-I1)") (class "Default")
      (node (ref "E16") (pin "2") (pinfunction "I1_2") (pintype "input"))
      (node (ref "JP2") (pin "2") (pinfunction "2_2") (pintype "passive"))
      (node (ref "JP2") (pin "4") (pinfunction "4_4") (pintype "passive"))
      (node (ref "JP2") (pin "6") (pinfunction "6_6") (pintype "passive"))
    )
    (net (code "130") (name "Net-(E16A-I2)") (class "Default")
      (node (ref "E16") (pin "13") (pinfunction "I2_13") (pintype "input"))
      (node (ref "JP3") (pin "2") (pinfunction "2_2") (pintype "passive"))
      (node (ref "JP3") (pin "4") (pinfunction "4_4") (pintype "passive"))
    )
    (net (code "131") (name "Net-(E17A-I1)") (class "Default")
      (node (ref "E17") (pin "10") (pinfunction "I1_10") (pintype "input"))
      (node (ref "E17") (pin "12") (pinfunction "I2_12") (pintype "input"))
      (node (ref "E17") (pin "13") (pinfunction "I3_13") (pintype "input"))
      (node (ref "E17") (pin "2") (pinfunction "I1_2") (pintype "input"))
      (node (ref "E17") (pin "4") (pinfunction "I2_4") (pintype "input"))
      (node (ref "E17") (pin "5") (pinfunction "I3_5") (pintype "input"))
      (node (ref "E5") (pin "2") (pinfunction "I1_2") (pintype "input"))
      (node (ref "E5") (pin "4") (pinfunction "I2_4") (pintype "input"))
      (node (ref "E5") (pin "5") (pinfunction "I3_5") (pintype "input"))
      (node (ref "R5") (pin "2") (pinfunction "2_2") (pintype "passive"))
      (node (ref "R6") (pin "1") (pinfunction "1_1") (pintype "passive"))
    )
    (net (code "132") (name "Net-(E18A-O)") (class "Default")
      (node (ref "E18") (pin "6") (pinfunction "O_6") (pintype "output"))
      (node (ref "E26") (pin "10") (pinfunction "PRE_10") (pintype "input"))
      (node (ref "E26") (pin "4") (pinfunction "PRE_4") (pintype "input"))
      (node (ref "E27") (pin "10") (pinfunction "PRE_10") (pintype "input"))
      (node (ref "E27") (pin "4") (pinfunction "PRE_4") (pintype "input"))
      (node (ref "E52") (pin "10") (pinfunction "PRE_10") (pintype "input"))
      (node (ref "E52") (pin "4") (pinfunction "PRE_4") (pintype "input"))
      (node (ref "E53") (pin "10") (pinfunction "PRE_10") (pintype "input"))
      (node (ref "E53") (pin "4") (pinfunction "PRE_4") (pintype "input"))
      (node (ref "E6") (pin "10") (pinfunction "PRE_10") (pintype "input"))
      (node (ref "E6") (pin "4") (pinfunction "PRE_4") (pintype "input"))
      (node (ref "E9") (pin "10") (pinfunction "PRE_10") (pintype "input"))
      (node (ref "E9") (pin "4") (pinfunction "PRE_4") (pintype "input"))
    )
    (net (code "133") (name "Net-(E18B-O)") (class "Default")
      (node (ref "E18") (pin "8") (pinfunction "O_8") (pintype "output"))
      (node (ref "E28") (pin "2") (pinfunction "I1_2") (pintype "input"))
      (node (ref "E28") (pin "7") (pinfunction "I1_7") (pintype "input"))
      (node (ref "E29") (pin "2") (pinfunction "I1_2") (pintype "input"))
      (node (ref "E29") (pin "7") (pinfunction "I1_7") (pintype "input"))
      (node (ref "E32") (pin "2") (pinfunction "I1_2") (pintype "input"))
      (node (ref "E32") (pin "7") (pinfunction "I1_7") (pintype "input"))
      (node (ref "E33") (pin "2") (pinfunction "I1_2") (pintype "input"))
      (node (ref "E33") (pin "7") (pinfunction "I1_7") (pintype "input"))
      (node (ref "E34") (pin "2") (pinfunction "I1_2") (pintype "input"))
      (node (ref "E34") (pin "7") (pinfunction "I1_7") (pintype "input"))
      (node (ref "E41") (pin "2") (pinfunction "I1_2") (pintype "input"))
      (node (ref "E41") (pin "7") (pinfunction "I1_7") (pintype "input"))
    )
    (net (code "134") (name "Net-(E20A-~{Q})") (class "Default")
      (node (ref "E20") (pin "6") (pinfunction "~{Q}_6") (pintype "output"))
      (node (ref "E8") (pin "5") (pinfunction "I3_5") (pintype "input"))
    )
    (net (code "135") (name "Net-(E20B-PRE)") (class "Default")
      (node (ref "E20") (pin "10") (pinfunction "PRE_10") (pintype "input"))
      (node (ref "E24") (pin "6") (pinfunction "O_6") (pintype "output"))
    )
    (net (code "136") (name "Net-(E20B-~{Q})") (class "Default")
      (node (ref "E20") (pin "8") (pinfunction "~{Q}_8") (pintype "output"))
      (node (ref "E8") (pin "13") (pinfunction "I3_13") (pintype "input"))
    )
    (net (code "137") (name "Net-(E21A-I1)") (class "Default")
      (node (ref "E21") (pin "10") (pinfunction "I1_10") (pintype "input"))
      (node (ref "E21") (pin "12") (pinfunction "I2_12") (pintype "input"))
      (node (ref "E21") (pin "13") (pinfunction "I3_13") (pintype "input"))
      (node (ref "E21") (pin "2") (pinfunction "I1_2") (pintype "input"))
      (node (ref "E21") (pin "4") (pinfunction "I2_4") (pintype "input"))
      (node (ref "E21") (pin "5") (pinfunction "I3_5") (pintype "input"))
      (node (ref "E47") (pin "10") (pinfunction "I1_10") (pintype "input"))
      (node (ref "E47") (pin "12") (pinfunction "I2_12") (pintype "input"))
      (node (ref "E47") (pin "13") (pinfunction "I3_13") (pintype "input"))
      (node (ref "R7") (pin "1") (pinfunction "1_1") (pintype "passive"))
      (node (ref "R8") (pin "2") (pinfunction "2_2") (pintype "passive"))
    )
    (net (code "138") (name "Net-(E22B-I0)") (class "Default")
      (node (ref "E22") (pin "9") (pinfunction "I0_9") (pintype "input"))
      (node (ref "PAD16") (pin "1") (pinfunction "P_1") (pintype "passive"))
    )
    (net (code "139") (name "Net-(E22B-I1)") (class "Default")
      (node (ref "E22") (pin "10") (pinfunction "I1_10") (pintype "input"))
      (node (ref "PAD17") (pin "1") (pinfunction "P_1") (pintype "passive"))
    )
    (net (code "140") (name "Net-(E22B-I2)") (class "Default")
      (node (ref "E22") (pin "12") (pinfunction "I2_12") (pintype "input"))
      (node (ref "PAD18") (pin "1") (pinfunction "P_1") (pintype "passive"))
    )
    (net (code "141") (name "Net-(E22B-I3)") (class "Default")
      (node (ref "E22") (pin "13") (pinfunction "I3_13") (pintype "input"))
      (node (ref "PAD19") (pin "1") (pinfunction "P_1") (pintype "passive"))
    )
    (net (code "142") (name "Net-(E22B-O)") (class "Default")
      (node (ref "E22") (pin "8") (pinfunction "O_8") (pintype "output"))
      (node (ref "PAD20") (pin "1") (pinfunction "P_1") (pintype "passive"))
    )
    (net (code "143") (name "Net-(E23E-I)") (class "Default")
      (node (ref "E23") (pin "11") (pinfunction "I_11") (pintype "input"))
      (node (ref "PAD12") (pin "1") (pinfunction "P_1") (pintype "passive"))
    )
    (net (code "144") (name "Net-(E23E-O)") (class "Default")
      (node (ref "E23") (pin "10") (pinfunction "O_10") (pintype "output"))
      (node (ref "PAD13") (pin "1") (pinfunction "P_1") (pintype "passive"))
    )
    (net (code "145") (name "Net-(E23F-I)") (class "Default")
      (node (ref "E23") (pin "13") (pinfunction "I_13") (pintype "input"))
      (node (ref "PAD14") (pin "1") (pinfunction "P_1") (pintype "passive"))
    )
    (net (code "146") (name "Net-(E23F-O)") (class "Default")
      (node (ref "E23") (pin "12") (pinfunction "O_12") (pintype "output"))
      (node (ref "PAD15") (pin "1") (pinfunction "P_1") (pintype "passive"))
    )
    (net (code "147") (name "Net-(E24C-I0)") (class "Default")
      (node (ref "E24") (pin "9") (pinfunction "I0_9") (pintype "input"))
      (node (ref "PAD27") (pin "1") (pinfunction "P_1") (pintype "passive"))
    )
    (net (code "148") (name "Net-(E24C-I1)") (class "Default")
      (node (ref "E24") (pin "10") (pinfunction "I1_10") (pintype "input"))
      (node (ref "PAD28") (pin "1") (pinfunction "P_1") (pintype "passive"))
    )
    (net (code "149") (name "Net-(E24C-I2)") (class "Default")
      (node (ref "E24") (pin "11") (pinfunction "I2_11") (pintype "input"))
      (node (ref "PAD29") (pin "1") (pinfunction "P_1") (pintype "passive"))
    )
    (net (code "150") (name "Net-(E24C-O)") (class "Default")
      (node (ref "E24") (pin "8") (pinfunction "O_8") (pintype "output"))
      (node (ref "PAD30") (pin "1") (pinfunction "P_1") (pintype "passive"))
    )
    (net (code "151") (name "Net-(E26A-CLK)") (class "Default")
      (node (ref "E26") (pin "11") (pinfunction "CLK_11") (pintype "input"))
      (node (ref "E26") (pin "3") (pinfunction "CLK_3") (pintype "input"))
      (node (ref "E27") (pin "11") (pinfunction "CLK_11") (pintype "input"))
      (node (ref "E27") (pin "3") (pinfunction "CLK_3") (pintype "input"))
      (node (ref "E49") (pin "6") (pinfunction "O_6") (pintype "output"))
    )
    (net (code "152") (name "Net-(E26A-~{Q})") (class "Default")
      (node (ref "E26") (pin "6") (pinfunction "~{Q}_6") (pintype "output"))
      (node (ref "E33") (pin "6") (pinfunction "I0_6") (pintype "input"))
    )
    (net (code "153") (name "Net-(E26B-~{Q})") (class "Default")
      (node (ref "E26") (pin "8") (pinfunction "~{Q}_8") (pintype "output"))
      (node (ref "E33") (pin "1") (pinfunction "I0_1") (pintype "input"))
    )
    (net (code "154") (name "Net-(E27A-~{Q})") (class "Default")
      (node (ref "E27") (pin "6") (pinfunction "~{Q}_6") (pintype "output"))
      (node (ref "E34") (pin "6") (pinfunction "I0_6") (pintype "input"))
    )
    (net (code "155") (name "Net-(E27B-~{Q})") (class "Default")
      (node (ref "E27") (pin "8") (pinfunction "~{Q}_8") (pintype "output"))
      (node (ref "E34") (pin "1") (pinfunction "I0_1") (pintype "input"))
    )
    (net (code "156") (name "Net-(E28A-I0)") (class "Default")
      (node (ref "E28") (pin "1") (pinfunction "I0_1") (pintype "input"))
      (node (ref "E53") (pin "8") (pinfunction "~{Q}_8") (pintype "output"))
    )
    (net (code "157") (name "Net-(E28B-I0)") (class "Default")
      (node (ref "E28") (pin "6") (pinfunction "I0_6") (pintype "input"))
      (node (ref "E53") (pin "6") (pinfunction "~{Q}_6") (pintype "output"))
    )
    (net (code "158") (name "Net-(E29A-I0)") (class "Default")
      (node (ref "E29") (pin "1") (pinfunction "I0_1") (pintype "input"))
      (node (ref "E52") (pin "8") (pinfunction "~{Q}_8") (pintype "output"))
    )
    (net (code "159") (name "Net-(E29B-I0)") (class "Default")
      (node (ref "E29") (pin "6") (pinfunction "I0_6") (pintype "input"))
      (node (ref "E52") (pin "6") (pinfunction "~{Q}_6") (pintype "output"))
    )
    (net (code "160") (name "Net-(E30A-I0)") (class "Default")
      (node (ref "E30") (pin "1") (pinfunction "I0_1") (pintype "input"))
      (node (ref "E7") (pin "8") (pinfunction "O_8") (pintype "output"))
    )
    (net (code "161") (name "Net-(E31A-I0)") (class "Default")
      (node (ref "E31") (pin "1") (pinfunction "I0_1") (pintype "input"))
      (node (ref "E35") (pin "10") (pinfunction "TAP3_10") (pintype "output"))
      (node (ref "IC2") (pin "6") (pinfunction "TAP3_6") (pintype "output"))
    )
    (net (code "162") (name "Net-(E31A-I1)") (class "Default")
      (node (ref "E31") (pin "2") (pinfunction "I1_2") (pintype "input"))
      (node (ref "E31") (pin "6") (pinfunction "O_6") (pintype "output"))
      (node (ref "E36") (pin "1") (pinfunction "I0_1") (pintype "input"))
      (node (ref "E36") (pin "2") (pinfunction "I1_2") (pintype "input"))
      (node (ref "E36") (pin "4") (pinfunction "I2_4") (pintype "input"))
      (node (ref "E36") (pin "5") (pinfunction "I3_5") (pintype "input"))
    )
    (net (code "163") (name "Net-(E31A-O)") (class "Default")
      (node (ref "C4") (pin "1") (pinfunction "1_1") (pintype "passive"))
      (node (ref "E31") (pin "3") (pinfunction "O_3") (pintype "output"))
      (node (ref "R28") (pin "1") (pinfunction "1_1") (pintype "passive"))
    )
    (net (code "164") (name "Net-(E31B-I0)") (class "Default")
      (node (ref "C4") (pin "2") (pinfunction "2_2") (pintype "passive"))
      (node (ref "D4") (pin "C") (pinfunction "C_C") (pintype "passive"))
      (node (ref "E31") (pin "4") (pinfunction "I0_4") (pintype "input"))
      (node (ref "E31") (pin "5") (pinfunction "I1_5") (pintype "input"))
      (node (ref "R27") (pin "2") (pinfunction "2_2") (pintype "passive"))
    )
    (net (code "165") (name "Net-(E31C-I0)") (class "Default")
      (node (ref "C3") (pin "2") (pinfunction "2_2") (pintype "passive"))
      (node (ref "D3") (pin "C") (pinfunction "C_C") (pintype "passive"))
      (node (ref "E31") (pin "10") (pinfunction "I1_10") (pintype "input"))
      (node (ref "E31") (pin "9") (pinfunction "I0_9") (pintype "input"))
      (node (ref "R25") (pin "2") (pinfunction "2_2") (pintype "passive"))
    )
    (net (code "166") (name "Net-(E31C-O)") (class "Default")
      (node (ref "E31") (pin "13") (pinfunction "I1_13") (pintype "input"))
      (node (ref "E31") (pin "8") (pinfunction "O_8") (pintype "output"))
      (node (ref "E36") (pin "10") (pinfunction "I1_10") (pintype "input"))
      (node (ref "E36") (pin "12") (pinfunction "I2_12") (pintype "input"))
      (node (ref "E36") (pin "13") (pinfunction "I3_13") (pintype "input"))
      (node (ref "E36") (pin "9") (pinfunction "I0_9") (pintype "input"))
    )
    (net (code "167") (name "Net-(E31D-I0)") (class "Default")
      (node (ref "E31") (pin "12") (pinfunction "I0_12") (pintype "input"))
      (node (ref "E35") (pin "4") (pinfunction "TAP2_4") (pintype "output"))
      (node (ref "IC2") (pin "2") (pinfunction "TAP2_2") (pintype "output"))
    )
    (net (code "168") (name "Net-(E31D-O)") (class "Default")
      (node (ref "C3") (pin "1") (pinfunction "1_1") (pintype "passive"))
      (node (ref "E31") (pin "11") (pinfunction "O_11") (pintype "output"))
      (node (ref "R26") (pin "1") (pinfunction "1_1") (pintype "passive"))
    )
    (net (code "169") (name "Net-(E32A-I0)") (class "Default")
      (node (ref "E32") (pin "1") (pinfunction "I0_1") (pintype "input"))
      (node (ref "E6") (pin "8") (pinfunction "~{Q}_8") (pintype "output"))
    )
    (net (code "170") (name "Net-(E32B-I0)") (class "Default")
      (node (ref "E32") (pin "6") (pinfunction "I0_6") (pintype "input"))
      (node (ref "E6") (pin "6") (pinfunction "~{Q}_6") (pintype "output"))
    )
    (net (code "171") (name "Net-(E35G-TAP1)") (class "Default")
      (node (ref "E35") (pin "12") (pinfunction "TAP1_12") (pintype "output"))
      (node (ref "IC2") (pin "7") (pinfunction "TAP1_7") (pintype "output"))
    )
    (net (code "172") (name "Net-(E35G-TAP4)") (class "Default")
      (node (ref "E35") (pin "6") (pinfunction "TAP4_6") (pintype "output"))
      (node (ref "IC2") (pin "3") (pinfunction "TAP4_3") (pintype "output"))
    )
    (net (code "173") (name "Net-(E35G-TAP5)") (class "Default")
      (node (ref "E35") (pin "8") (pinfunction "TAP5_8") (pintype "output"))
      (node (ref "IC2") (pin "5") (pinfunction "TAP5_5") (pintype "output"))
    )
    (net (code "174") (name "Net-(E37A-I1)") (class "Default")
      (node (ref "E37") (pin "2") (pinfunction "I1_2") (pintype "input"))
      (node (ref "E37") (pin "6") (pinfunction "O_6") (pintype "output"))
      (node (ref "E40") (pin "1") (pinfunction "I0_1") (pintype "input"))
      (node (ref "E40") (pin "2") (pinfunction "I1_2") (pintype "input"))
      (node (ref "E40") (pin "4") (pinfunction "I2_4") (pintype "input"))
      (node (ref "E40") (pin "5") (pinfunction "I3_5") (pintype "input"))
    )
    (net (code "175") (name "Net-(E37A-O)") (class "Default")
      (node (ref "C5") (pin "1") (pinfunction "1_1") (pintype "passive"))
      (node (ref "E37") (pin "3") (pinfunction "O_3") (pintype "output"))
      (node (ref "R30") (pin "1") (pinfunction "1_1") (pintype "passive"))
    )
    (net (code "176") (name "Net-(E37B-I0)") (class "Default")
      (node (ref "C5") (pin "2") (pinfunction "2_2") (pintype "passive"))
      (node (ref "D5") (pin "C") (pinfunction "C_C") (pintype "passive"))
      (node (ref "E37") (pin "4") (pinfunction "I0_4") (pintype "input"))
      (node (ref "E37") (pin "5") (pinfunction "I1_5") (pintype "input"))
      (node (ref "R29") (pin "2") (pinfunction "2_2") (pintype "passive"))
    )
    (net (code "177") (name "Net-(E37C-I0)") (class "Default")
      (node (ref "E37") (pin "9") (pinfunction "I0_9") (pintype "input"))
      (node (ref "PAD31") (pin "1") (pinfunction "P_1") (pintype "passive"))
    )
    (net (code "178") (name "Net-(E37C-I1)") (class "Default")
      (node (ref "E37") (pin "10") (pinfunction "I1_10") (pintype "input"))
      (node (ref "PAD32") (pin "1") (pinfunction "P_1") (pintype "passive"))
    )
    (net (code "179") (name "Net-(E37C-O)") (class "Default")
      (node (ref "E37") (pin "8") (pinfunction "O_8") (pintype "output"))
      (node (ref "PAD33") (pin "1") (pinfunction "P_1") (pintype "passive"))
    )
    (net (code "180") (name "Net-(E37D-I0)") (class "Default")
      (node (ref "E37") (pin "12") (pinfunction "I0_12") (pintype "input"))
      (node (ref "PAD34") (pin "1") (pinfunction "P_1") (pintype "passive"))
    )
    (net (code "181") (name "Net-(E37D-I1)") (class "Default")
      (node (ref "E37") (pin "13") (pinfunction "I1_13") (pintype "input"))
      (node (ref "PAD35") (pin "1") (pinfunction "P_1") (pintype "passive"))
    )
    (net (code "182") (name "Net-(E37D-O)") (class "Default")
      (node (ref "E37") (pin "11") (pinfunction "O_11") (pintype "output"))
      (node (ref "PAD36") (pin "1") (pinfunction "P_1") (pintype "passive"))
    )
    (net (code "183") (name "Net-(E38G-IN)") (class "Default")
      (node (ref "E38") (pin "1") (pinfunction "IN_1") (pintype "input"))
      (node (ref "E7") (pin "12") (pinfunction "O_12") (pintype "output"))
      (node (ref "IC1") (pin "1") (pinfunction "IN_1") (pintype "input"))
    )
    (net (code "184") (name "Net-(E38G-TAP1)") (class "Default")
      (node (ref "E38") (pin "12") (pinfunction "TAP1_12") (pintype "output"))
      (node (ref "E39") (pin "12") (pinfunction "I0_12") (pintype "input"))
      (node (ref "IC1") (pin "7") (pinfunction "TAP1_7") (pintype "output"))
    )
    (net (code "185") (name "Net-(E38G-TAP2)") (class "Default")
      (node (ref "E38") (pin "4") (pinfunction "TAP2_4") (pintype "output"))
      (node (ref "IC1") (pin "2") (pinfunction "TAP2_2") (pintype "output"))
    )
    (net (code "186") (name "Net-(E38G-TAP3)") (class "Default")
      (node (ref "E38") (pin "10") (pinfunction "TAP3_10") (pintype "output"))
      (node (ref "IC1") (pin "6") (pinfunction "TAP3_6") (pintype "output"))
    )
    (net (code "187") (name "Net-(E38G-TAP4)") (class "Default")
      (node (ref "E38") (pin "6") (pinfunction "TAP4_6") (pintype "output"))
      (node (ref "E39") (pin "1") (pinfunction "I0_1") (pintype "input"))
      (node (ref "IC1") (pin "3") (pinfunction "TAP4_3") (pintype "output"))
    )
    (net (code "188") (name "Net-(E38G-TAP5)") (class "Default")
      (node (ref "E38") (pin "8") (pinfunction "TAP5_8") (pintype "output"))
      (node (ref "IC1") (pin "5") (pinfunction "TAP5_5") (pintype "output"))
    )
    (net (code "189") (name "Net-(E39A-I1)") (class "Default")
      (node (ref "E39") (pin "2") (pinfunction "I1_2") (pintype "input"))
      (node (ref "E39") (pin "6") (pinfunction "O_6") (pintype "output"))
      (node (ref "E44") (pin "1") (pinfunction "I0_1") (pintype "input"))
      (node (ref "E44") (pin "2") (pinfunction "I1_2") (pintype "input"))
      (node (ref "E44") (pin "4") (pinfunction "I2_4") (pintype "input"))
      (node (ref "E44") (pin "5") (pinfunction "I3_5") (pintype "input"))
    )
    (net (code "190") (name "Net-(E39A-O)") (class "Default")
      (node (ref "C2") (pin "1") (pinfunction "1_1") (pintype "passive"))
      (node (ref "E39") (pin "3") (pinfunction "O_3") (pintype "output"))
      (node (ref "R22") (pin "1") (pinfunction "1_1") (pintype "passive"))
    )
    (net (code "191") (name "Net-(E39B-I0)") (class "Default")
      (node (ref "C2") (pin "2") (pinfunction "2_2") (pintype "passive"))
      (node (ref "D2") (pin "C") (pinfunction "C_C") (pintype "passive"))
      (node (ref "E39") (pin "4") (pinfunction "I0_4") (pintype "input"))
      (node (ref "E39") (pin "5") (pinfunction "I1_5") (pintype "input"))
      (node (ref "R21") (pin "2") (pinfunction "2_2") (pintype "passive"))
    )
    (net (code "192") (name "Net-(E39C-I0)") (class "Default")
      (node (ref "C1") (pin "2") (pinfunction "2_2") (pintype "passive"))
      (node (ref "D1") (pin "C") (pinfunction "C_C") (pintype "passive"))
      (node (ref "E39") (pin "10") (pinfunction "I1_10") (pintype "input"))
      (node (ref "E39") (pin "9") (pinfunction "I0_9") (pintype "input"))
      (node (ref "R19") (pin "2") (pinfunction "2_2") (pintype "passive"))
    )
    (net (code "193") (name "Net-(E39C-O)") (class "Default")
      (node (ref "E39") (pin "13") (pinfunction "I1_13") (pintype "input"))
      (node (ref "E39") (pin "8") (pinfunction "O_8") (pintype "output"))
      (node (ref "E44") (pin "10") (pinfunction "I1_10") (pintype "input"))
      (node (ref "E44") (pin "12") (pinfunction "I2_12") (pintype "input"))
      (node (ref "E44") (pin "13") (pinfunction "I3_13") (pintype "input"))
      (node (ref "E44") (pin "9") (pinfunction "I0_9") (pintype "input"))
    )
    (net (code "194") (name "Net-(E39D-O)") (class "Default")
      (node (ref "C1") (pin "1") (pinfunction "1_1") (pintype "passive"))
      (node (ref "E39") (pin "11") (pinfunction "O_11") (pintype "output"))
      (node (ref "R20") (pin "1") (pinfunction "1_1") (pintype "passive"))
    )
    (net (code "195") (name "Net-(E40B-I0)") (class "Default")
      (node (ref "E40") (pin "9") (pinfunction "I0_9") (pintype "input"))
      (node (ref "PAD37") (pin "1") (pinfunction "P_1") (pintype "passive"))
    )
    (net (code "196") (name "Net-(E40B-I1)") (class "Default")
      (node (ref "E40") (pin "10") (pinfunction "I1_10") (pintype "input"))
      (node (ref "PAD38") (pin "1") (pinfunction "P_1") (pintype "passive"))
    )
    (net (code "197") (name "Net-(E40B-I2)") (class "Default")
      (node (ref "E40") (pin "12") (pinfunction "I2_12") (pintype "input"))
      (node (ref "PAD39") (pin "1") (pinfunction "P_1") (pintype "passive"))
    )
    (net (code "198") (name "Net-(E40B-I3)") (class "Default")
      (node (ref "E40") (pin "13") (pinfunction "I3_13") (pintype "input"))
      (node (ref "PAD40") (pin "1") (pinfunction "P_1") (pintype "passive"))
    )
    (net (code "199") (name "Net-(E40B-O)") (class "Default")
      (node (ref "E40") (pin "8") (pinfunction "O_8") (pintype "output"))
      (node (ref "PAD41") (pin "1") (pinfunction "P_1") (pintype "passive"))
    )
    (net (code "200") (name "Net-(E41A-I0)") (class "Default")
      (node (ref "E41") (pin "1") (pinfunction "I0_1") (pintype "input"))
      (node (ref "E9") (pin "8") (pinfunction "~{Q}_8") (pintype "output"))
    )
    (net (code "201") (name "Net-(E41B-I0)") (class "Default")
      (node (ref "E41") (pin "6") (pinfunction "I0_6") (pintype "input"))
      (node (ref "E9") (pin "6") (pinfunction "~{Q}_6") (pintype "output"))
    )
    (net (code "202") (name "Net-(E47A-I1)") (class "Default")
      (node (ref "E47") (pin "2") (pinfunction "I1_2") (pintype "input"))
      (node (ref "E47") (pin "4") (pinfunction "I2_4") (pintype "input"))
      (node (ref "E47") (pin "5") (pinfunction "I3_5") (pintype "input"))
      (node (ref "E48") (pin "10") (pinfunction "I1_10") (pintype "input"))
      (node (ref "E48") (pin "12") (pinfunction "I2_12") (pintype "input"))
      (node (ref "E48") (pin "13") (pinfunction "I3_13") (pintype "input"))
      (node (ref "E48") (pin "2") (pinfunction "I1_2") (pintype "input"))
      (node (ref "E48") (pin "4") (pinfunction "I2_4") (pintype "input"))
      (node (ref "E48") (pin "5") (pinfunction "I3_5") (pintype "input"))
      (node (ref "R10") (pin "1") (pinfunction "1_1") (pintype "passive"))
      (node (ref "R9") (pin "2") (pinfunction "2_2") (pintype "passive"))
    )
    (net (code "203") (name "Net-(E49A-O)") (class "Default")
      (node (ref "E49") (pin "3") (pinfunction "O_3") (pintype "output"))
      (node (ref "E6") (pin "11") (pinfunction "CLK_11") (pintype "input"))
      (node (ref "E6") (pin "3") (pinfunction "CLK_3") (pintype "input"))
      (node (ref "E9") (pin "11") (pinfunction "CLK_11") (pintype "input"))
      (node (ref "E9") (pin "3") (pinfunction "CLK_3") (pintype "input"))
    )
    (net (code "204") (name "Net-(E49C-O)") (class "Default")
      (node (ref "E49") (pin "8") (pinfunction "O_8") (pintype "output"))
      (node (ref "E52") (pin "11") (pinfunction "CLK_11") (pintype "input"))
      (node (ref "E52") (pin "3") (pinfunction "CLK_3") (pintype "input"))
      (node (ref "E53") (pin "11") (pinfunction "CLK_11") (pintype "input"))
      (node (ref "E53") (pin "3") (pinfunction "CLK_3") (pintype "input"))
    )
    (net (code "205") (name "Net-(E49D-I0)") (class "Default")
      (node (ref "E49") (pin "12") (pinfunction "I0_12") (pintype "input"))
      (node (ref "PAD42") (pin "1") (pinfunction "P_1") (pintype "passive"))
    )
    (net (code "206") (name "Net-(E49D-I1)") (class "Default")
      (node (ref "E49") (pin "13") (pinfunction "I1_13") (pintype "input"))
      (node (ref "PAD43") (pin "1") (pinfunction "P_1") (pintype "passive"))
    )
    (net (code "207") (name "Net-(E49D-O)") (class "Default")
      (node (ref "E49") (pin "11") (pinfunction "O_11") (pintype "output"))
      (node (ref "PAD44") (pin "1") (pinfunction "P_1") (pintype "passive"))
    )
    (net (code "208") (name "VCC") (class "Default")
      (node (ref "R1") (pin "1") (pinfunction "1_1") (pintype "passive"))
      (node (ref "R11") (pin "1") (pinfunction "1_1") (pintype "passive"))
      (node (ref "R13") (pin "1") (pinfunction "1_1") (pintype "passive"))
      (node (ref "R15") (pin "1") (pinfunction "1_1") (pintype "passive"))
      (node (ref "R17") (pin "1") (pinfunction "1_1") (pintype "passive"))
      (node (ref "R20") (pin "2") (pinfunction "2_2") (pintype "passive"))
      (node (ref "R22") (pin "2") (pinfunction "2_2") (pintype "passive"))
      (node (ref "R23") (pin "1") (pinfunction "1_1") (pintype "passive"))
      (node (ref "R26") (pin "2") (pinfunction "2_2") (pintype "passive"))
      (node (ref "R28") (pin "2") (pinfunction "2_2") (pintype "passive"))
      (node (ref "R3") (pin "1") (pinfunction "1_1") (pintype "passive"))
      (node (ref "R30") (pin "2") (pinfunction "2_2") (pintype "passive"))
      (node (ref "R5") (pin "1") (pinfunction "1_1") (pintype "passive"))
      (node (ref "R8") (pin "1") (pinfunction "1_1") (pintype "passive"))
      (node (ref "R9") (pin "1") (pinfunction "1_1") (pintype "passive"))
      (node (ref "U$1") (pin "AA2") (pinfunction "1_AA2") (pintype "bidirectional"))
      (node (ref "U$1") (pin "BA2") (pinfunction "1_BA2") (pintype "bidirectional"))
      (node (ref "U$1") (pin "CA2") (pinfunction "1_CA2") (pintype "bidirectional"))
      (node (ref "U$1") (pin "DA2") (pinfunction "1_DA2") (pintype "bidirectional"))
    )
    (net (code "209") (name "unconnected-(E6A-Q-Pad5)") (class "Default")
      (node (ref "E6") (pin "5") (pinfunction "Q_5") (pintype "output"))
    )
    (net (code "210") (name "unconnected-(E6B-Q-Pad9)") (class "Default")
      (node (ref "E6") (pin "9") (pinfunction "Q_9") (pintype "output"))
    )
    (net (code "211") (name "unconnected-(E9A-Q-Pad5)") (class "Default")
      (node (ref "E9") (pin "5") (pinfunction "Q_5") (pintype "output"))
    )
    (net (code "212") (name "unconnected-(E9B-Q-Pad9)") (class "Default")
      (node (ref "E9") (pin "9") (pinfunction "Q_9") (pintype "output"))
    )
    (net (code "213") (name "unconnected-(E10A-Q-Pad5)") (class "Default")
      (node (ref "E10") (pin "5") (pinfunction "Q_5") (pintype "output"))
    )
    (net (code "214") (name "unconnected-(E10B-Q-Pad9)") (class "Default")
      (node (ref "E10") (pin "9") (pinfunction "Q_9") (pintype "output"))
    )
    (net (code "215") (name "unconnected-(E14A-Q-Pad5)") (class "Default")
      (node (ref "E14") (pin "5") (pinfunction "Q_5") (pintype "output"))
    )
    (net (code "216") (name "unconnected-(E14B-Q-Pad9)") (class "Default")
      (node (ref "E14") (pin "9") (pinfunction "Q_9") (pintype "output"))
    )
    (net (code "217") (name "unconnected-(E15A-Q-Pad5)") (class "Default")
      (node (ref "E15") (pin "5") (pinfunction "Q_5") (pintype "output"))
    )
    (net (code "218") (name "unconnected-(E15B-Q-Pad9)") (class "Default")
      (node (ref "E15") (pin "9") (pinfunction "Q_9") (pintype "output"))
    )
    (net (code "219") (name "unconnected-(E20B-Q-Pad9)") (class "Default")
      (node (ref "E20") (pin "9") (pinfunction "Q_9") (pintype "output"))
    )
    (net (code "220") (name "unconnected-(E26A-Q-Pad5)") (class "Default")
      (node (ref "E26") (pin "5") (pinfunction "Q_5") (pintype "output"))
    )
    (net (code "221") (name "unconnected-(E26B-Q-Pad9)") (class "Default")
      (node (ref "E26") (pin "9") (pinfunction "Q_9") (pintype "output"))
    )
    (net (code "222") (name "unconnected-(E27A-Q-Pad5)") (class "Default")
      (node (ref "E27") (pin "5") (pinfunction "Q_5") (pintype "output"))
    )
    (net (code "223") (name "unconnected-(E27B-Q-Pad9)") (class "Default")
      (node (ref "E27") (pin "9") (pinfunction "Q_9") (pintype "output"))
    )
    (net (code "224") (name "unconnected-(E52A-Q-Pad5)") (class "Default")
      (node (ref "E52") (pin "5") (pinfunction "Q_5") (pintype "output"))
    )
    (net (code "225") (name "unconnected-(E52B-Q-Pad9)") (class "Default")
      (node (ref "E52") (pin "9") (pinfunction "Q_9") (pintype "output"))
    )
    (net (code "226") (name "unconnected-(E53A-Q-Pad5)") (class "Default")
      (node (ref "E53") (pin "5") (pinfunction "Q_5") (pintype "output"))
    )
    (net (code "227") (name "unconnected-(E53B-Q-Pad9)") (class "Default")
      (node (ref "E53") (pin "9") (pinfunction "Q_9") (pintype "output"))
    )
    (net (code "228") (name "unconnected-(H01/H20-Pad2)") (class "Default")
      (node (ref "H01/H20") (pin "2") (pinfunction "2_2") (pintype "passive"))
    )
    (net (code "229") (name "unconnected-(H01/H20-Pad4)") (class "Default")
      (node (ref "H01/H20") (pin "4") (pinfunction "4_4") (pintype "passive"))
    )
    (net (code "230") (name "unconnected-(H01/H20-Pad10)") (class "Default")
      (node (ref "H01/H20") (pin "10") (pinfunction "10_10") (pintype "passive"))
    )
    (net (code "231") (name "unconnected-(H01/H20-Pad14)") (class "Default")
      (node (ref "H01/H20") (pin "14") (pinfunction "14_14") (pintype "passive"))
    )
    (net (code "232") (name "unconnected-(H01/H20-Pad18)") (class "Default")
      (node (ref "H01/H20") (pin "18") (pinfunction "18_18") (pintype "passive"))
    )
    (net (code "233") (name "unconnected-(H01/H20-Pad22)") (class "Default")
      (node (ref "H01/H20") (pin "22") (pinfunction "22_22") (pintype "passive"))
    )
    (net (code "234") (name "unconnected-(H01/H20-Pad26)") (class "Default")
      (node (ref "H01/H20") (pin "26") (pinfunction "26_26") (pintype "passive"))
    )
    (net (code "235") (name "unconnected-(H01/H20-Pad34)") (class "Default")
      (node (ref "H01/H20") (pin "34") (pinfunction "34_34") (pintype "passive"))
    )
    (net (code "236") (name "unconnected-(H02/H21-Pad2)") (class "Default")
      (node (ref "H02/H21") (pin "2") (pinfunction "2_2") (pintype "passive"))
    )
    (net (code "237") (name "unconnected-(H02/H21-Pad4)") (class "Default")
      (node (ref "H02/H21") (pin "4") (pinfunction "4_4") (pintype "passive"))
    )
    (net (code "238") (name "unconnected-(H02/H21-Pad10)") (class "Default")
      (node (ref "H02/H21") (pin "10") (pinfunction "10_10") (pintype "passive"))
    )
    (net (code "239") (name "unconnected-(H02/H21-Pad14)") (class "Default")
      (node (ref "H02/H21") (pin "14") (pinfunction "14_14") (pintype "passive"))
    )
    (net (code "240") (name "unconnected-(H02/H21-Pad18)") (class "Default")
      (node (ref "H02/H21") (pin "18") (pinfunction "18_18") (pintype "passive"))
    )
    (net (code "241") (name "unconnected-(H02/H21-Pad22)") (class "Default")
      (node (ref "H02/H21") (pin "22") (pinfunction "22_22") (pintype "passive"))
    )
    (net (code "242") (name "unconnected-(H02/H21-Pad26)") (class "Default")
      (node (ref "H02/H21") (pin "26") (pinfunction "26_26") (pintype "passive"))
    )
    (net (code "243") (name "unconnected-(H02/H21-Pad34)") (class "Default")
      (node (ref "H02/H21") (pin "34") (pinfunction "34_34") (pintype "passive"))
    )
    (net (code "244") (name "unconnected-(H03/H22-Pad2)") (class "Default")
      (node (ref "H03/H22") (pin "2") (pinfunction "2_2") (pintype "passive"))
    )
    (net (code "245") (name "unconnected-(H03/H22-Pad4)") (class "Default")
      (node (ref "H03/H22") (pin "4") (pinfunction "4_4") (pintype "passive"))
    )
    (net (code "246") (name "unconnected-(H03/H22-Pad10)") (class "Default")
      (node (ref "H03/H22") (pin "10") (pinfunction "10_10") (pintype "passive"))
    )
    (net (code "247") (name "unconnected-(H03/H22-Pad14)") (class "Default")
      (node (ref "H03/H22") (pin "14") (pinfunction "14_14") (pintype "passive"))
    )
    (net (code "248") (name "unconnected-(H03/H22-Pad18)") (class "Default")
      (node (ref "H03/H22") (pin "18") (pinfunction "18_18") (pintype "passive"))
    )
    (net (code "249") (name "unconnected-(H03/H22-Pad22)") (class "Default")
      (node (ref "H03/H22") (pin "22") (pinfunction "22_22") (pintype "passive"))
    )
    (net (code "250") (name "unconnected-(H03/H22-Pad26)") (class "Default")
      (node (ref "H03/H22") (pin "26") (pinfunction "26_26") (pintype "passive"))
    )
    (net (code "251") (name "unconnected-(H03/H22-Pad34)") (class "Default")
      (node (ref "H03/H22") (pin "34") (pinfunction "34_34") (pintype "passive"))
    )
    (net (code "252") (name "unconnected-(H04/H23-Pad2)") (class "Default")
      (node (ref "H04/H23") (pin "2") (pinfunction "2_2") (pintype "passive"))
    )
    (net (code "253") (name "unconnected-(H04/H23-Pad4)") (class "Default")
      (node (ref "H04/H23") (pin "4") (pinfunction "4_4") (pintype "passive"))
    )
    (net (code "254") (name "unconnected-(H04/H23-Pad6)") (class "Default")
      (node (ref "H04/H23") (pin "6") (pinfunction "6_6") (pintype "passive"))
    )
    (net (code "255") (name "unconnected-(H04/H23-Pad10)") (class "Default")
      (node (ref "H04/H23") (pin "10") (pinfunction "10_10") (pintype "passive"))
    )
    (net (code "256") (name "unconnected-(H04/H23-Pad14)") (class "Default")
      (node (ref "H04/H23") (pin "14") (pinfunction "14_14") (pintype "passive"))
    )
    (net (code "257") (name "unconnected-(H04/H23-Pad18)") (class "Default")
      (node (ref "H04/H23") (pin "18") (pinfunction "18_18") (pintype "passive"))
    )
    (net (code "258") (name "unconnected-(H04/H23-Pad22)") (class "Default")
      (node (ref "H04/H23") (pin "22") (pinfunction "22_22") (pintype "passive"))
    )
    (net (code "259") (name "unconnected-(H04/H23-Pad26)") (class "Default")
      (node (ref "H04/H23") (pin "26") (pinfunction "26_26") (pintype "passive"))
    )
    (net (code "260") (name "unconnected-(H04/H23-Pad34)") (class "Default")
      (node (ref "H04/H23") (pin "34") (pinfunction "34_34") (pintype "passive"))
    )
    (net (code "261") (name "unconnected-(H05/H24-Pad2)") (class "Default")
      (node (ref "H05/H24") (pin "2") (pinfunction "2_2") (pintype "passive"))
    )
    (net (code "262") (name "unconnected-(H05/H24-Pad4)") (class "Default")
      (node (ref "H05/H24") (pin "4") (pinfunction "4_4") (pintype "passive"))
    )
    (net (code "263") (name "unconnected-(H05/H24-Pad10)") (class "Default")
      (node (ref "H05/H24") (pin "10") (pinfunction "10_10") (pintype "passive"))
    )
    (net (code "264") (name "unconnected-(H05/H24-Pad14)") (class "Default")
      (node (ref "H05/H24") (pin "14") (pinfunction "14_14") (pintype "passive"))
    )
    (net (code "265") (name "unconnected-(H05/H24-Pad18)") (class "Default")
      (node (ref "H05/H24") (pin "18") (pinfunction "18_18") (pintype "passive"))
    )
    (net (code "266") (name "unconnected-(H05/H24-Pad22)") (class "Default")
      (node (ref "H05/H24") (pin "22") (pinfunction "22_22") (pintype "passive"))
    )
    (net (code "267") (name "unconnected-(H05/H24-Pad26)") (class "Default")
      (node (ref "H05/H24") (pin "26") (pinfunction "26_26") (pintype "passive"))
    )
    (net (code "268") (name "unconnected-(H05/H24-Pad30)") (class "Default")
      (node (ref "H05/H24") (pin "30") (pinfunction "30_30") (pintype "passive"))
    )
    (net (code "269") (name "unconnected-(H05/H24-Pad34)") (class "Default")
      (node (ref "H05/H24") (pin "34") (pinfunction "34_34") (pintype "passive"))
    )
  )
)
